# controller.net
KiCad netlist of a schematic drawn in EAGLE
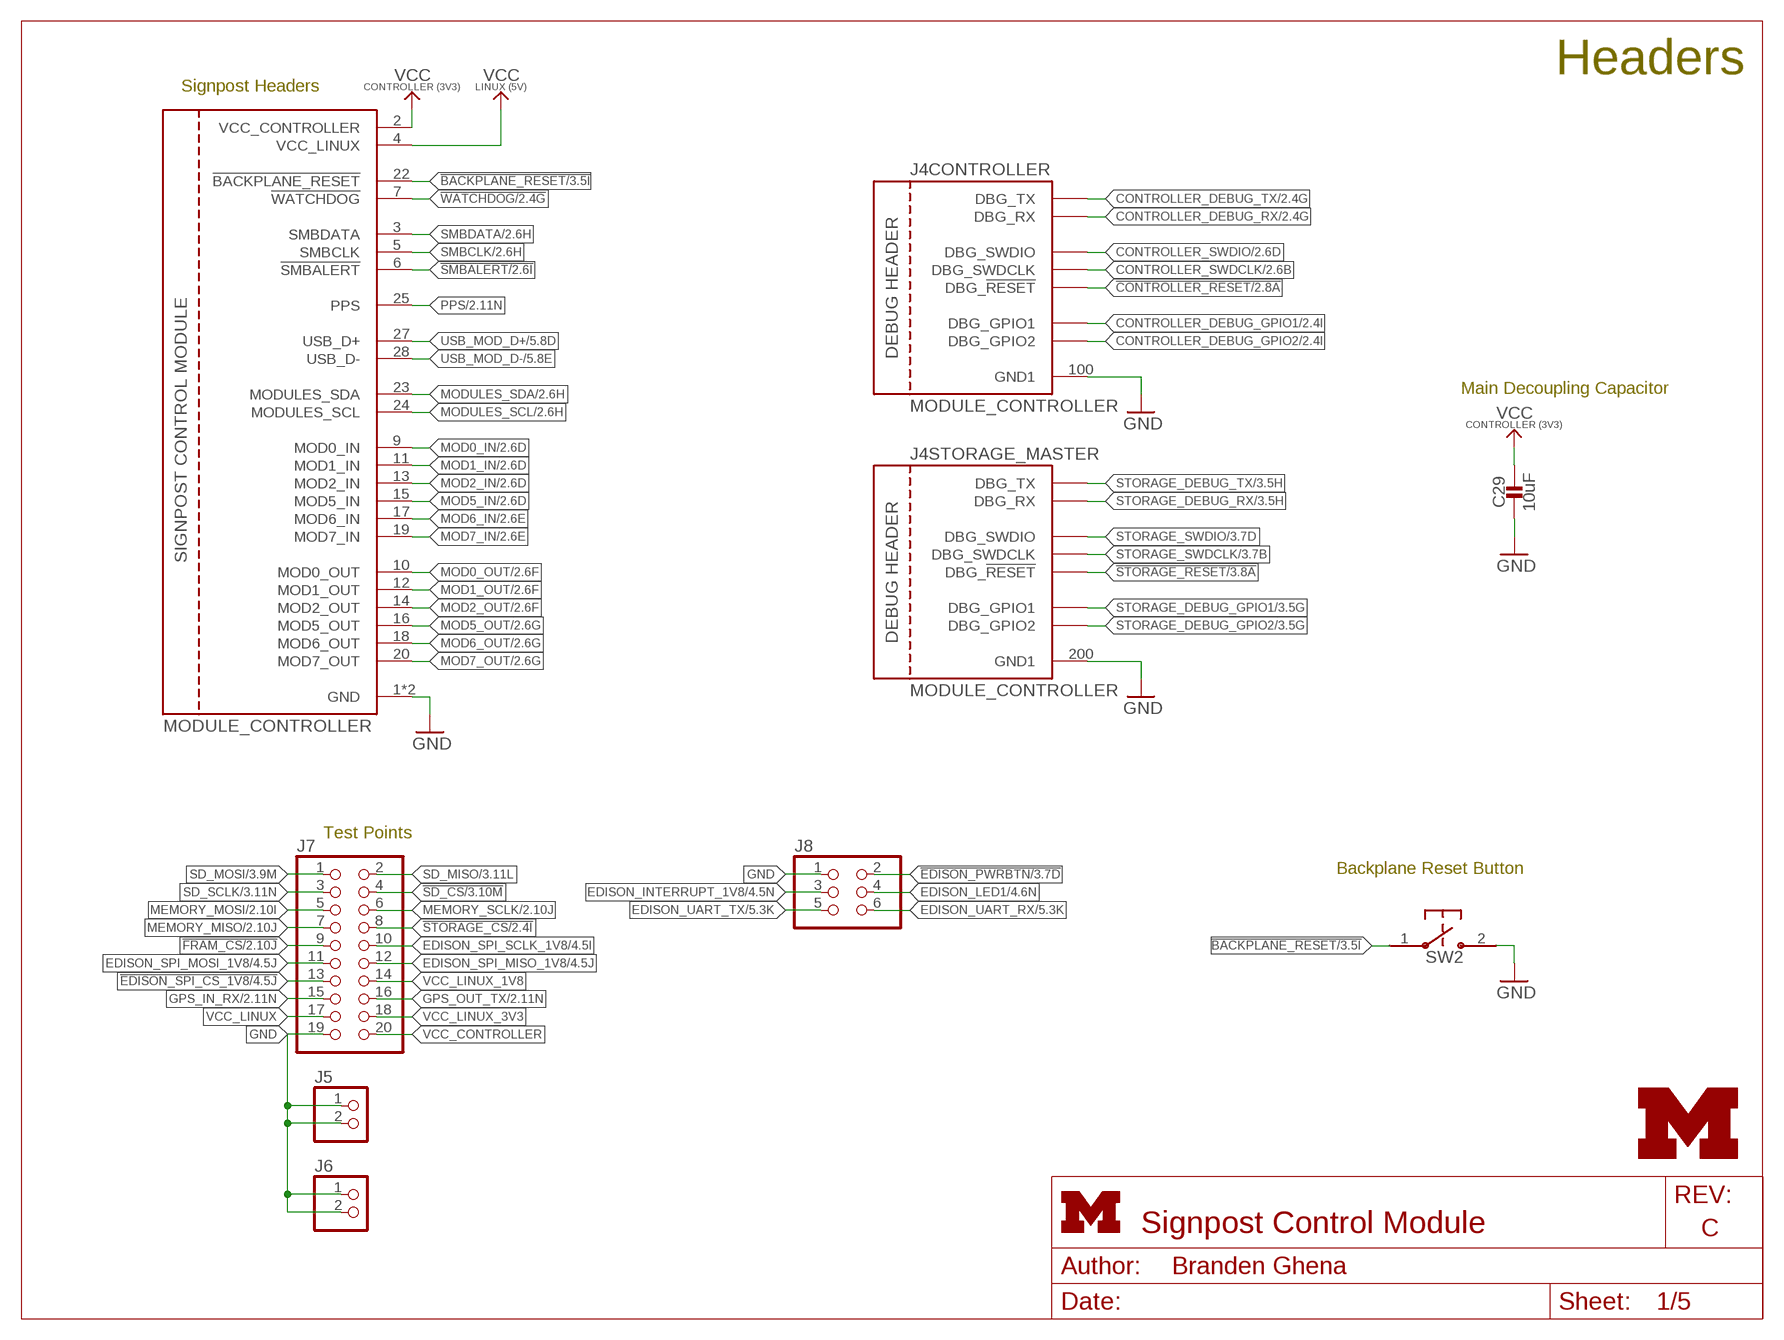
[diagram p0: schematic, sheet 1]
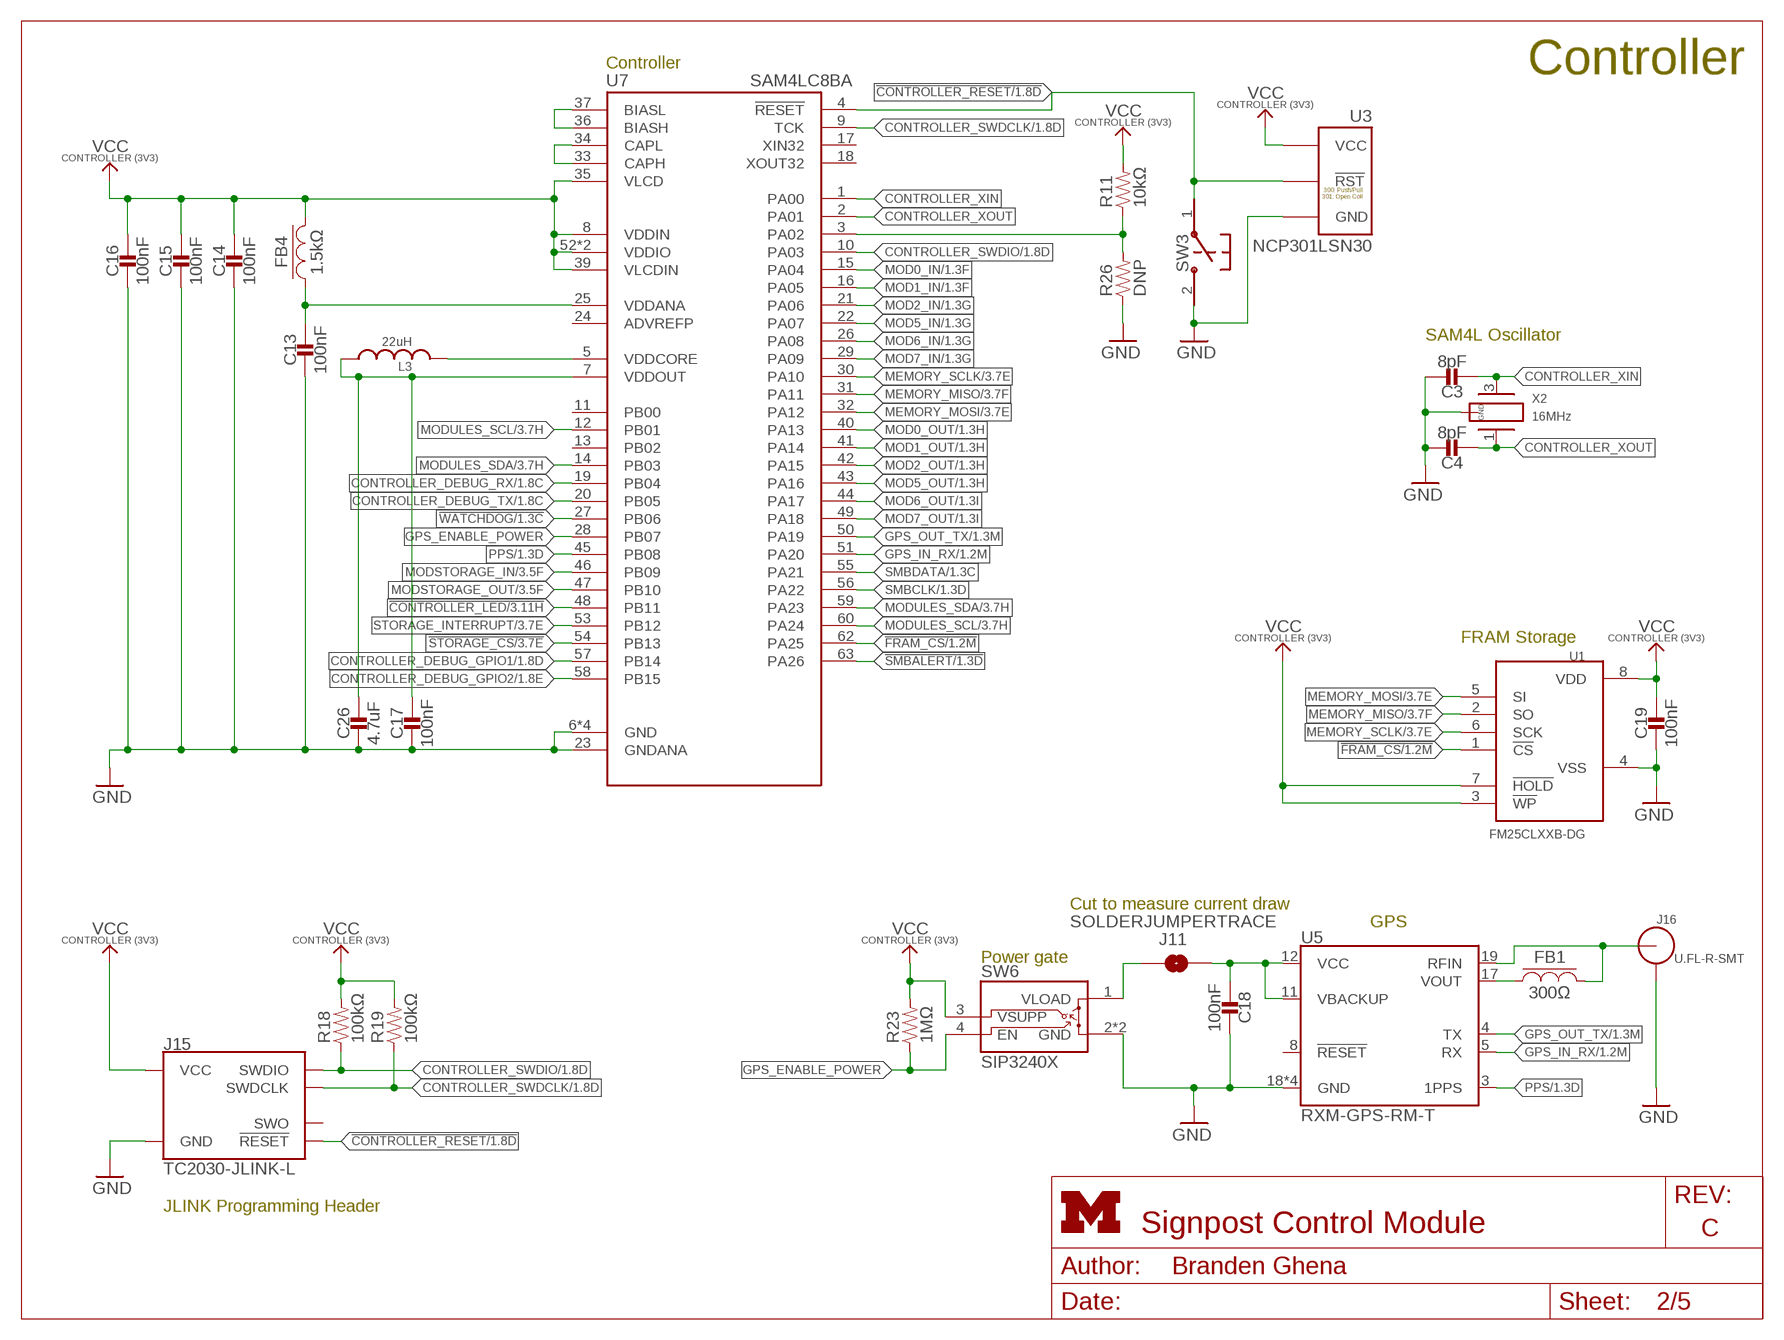
[diagram p1: schematic, sheet 2]
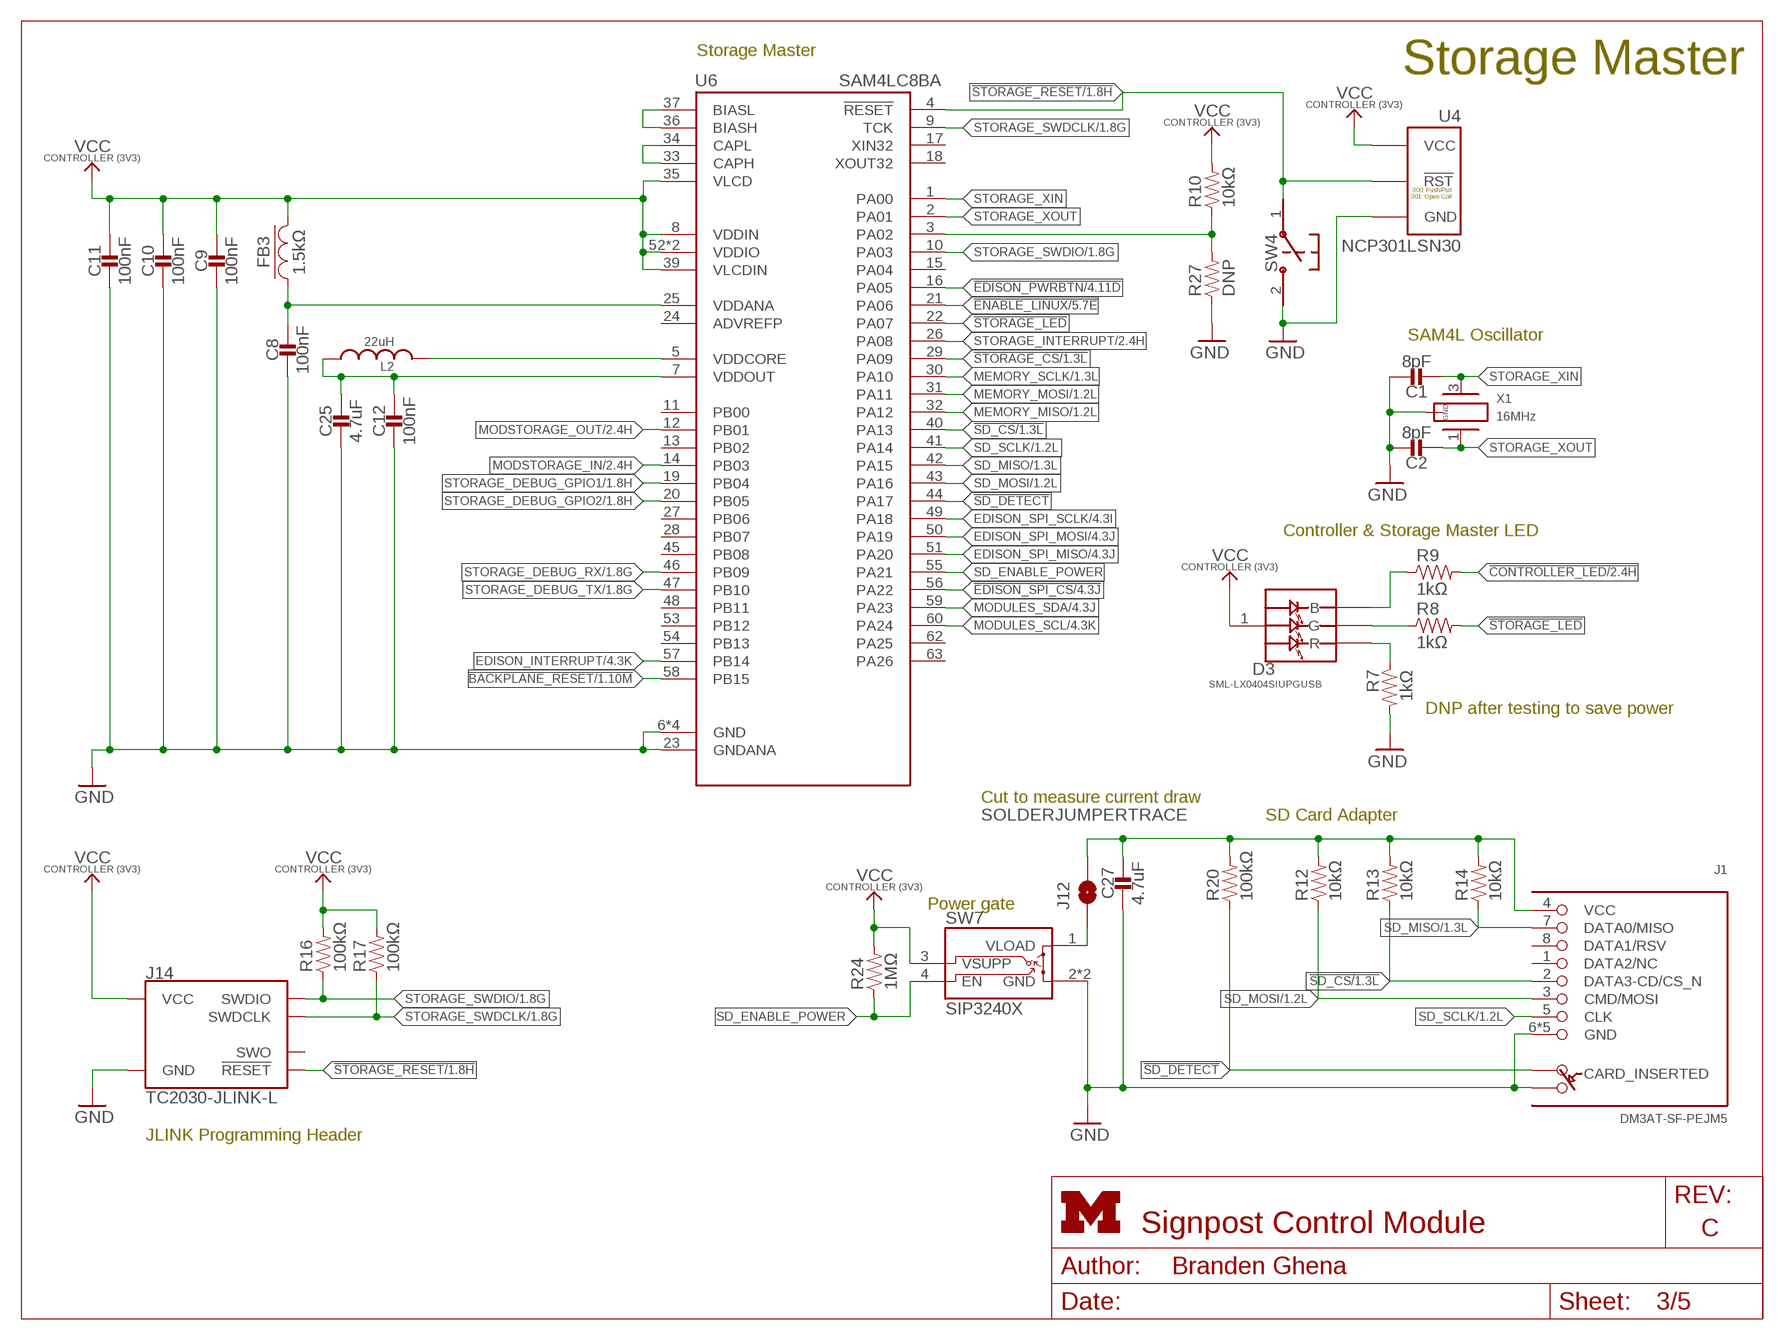
[diagram p2: schematic, sheet 3]
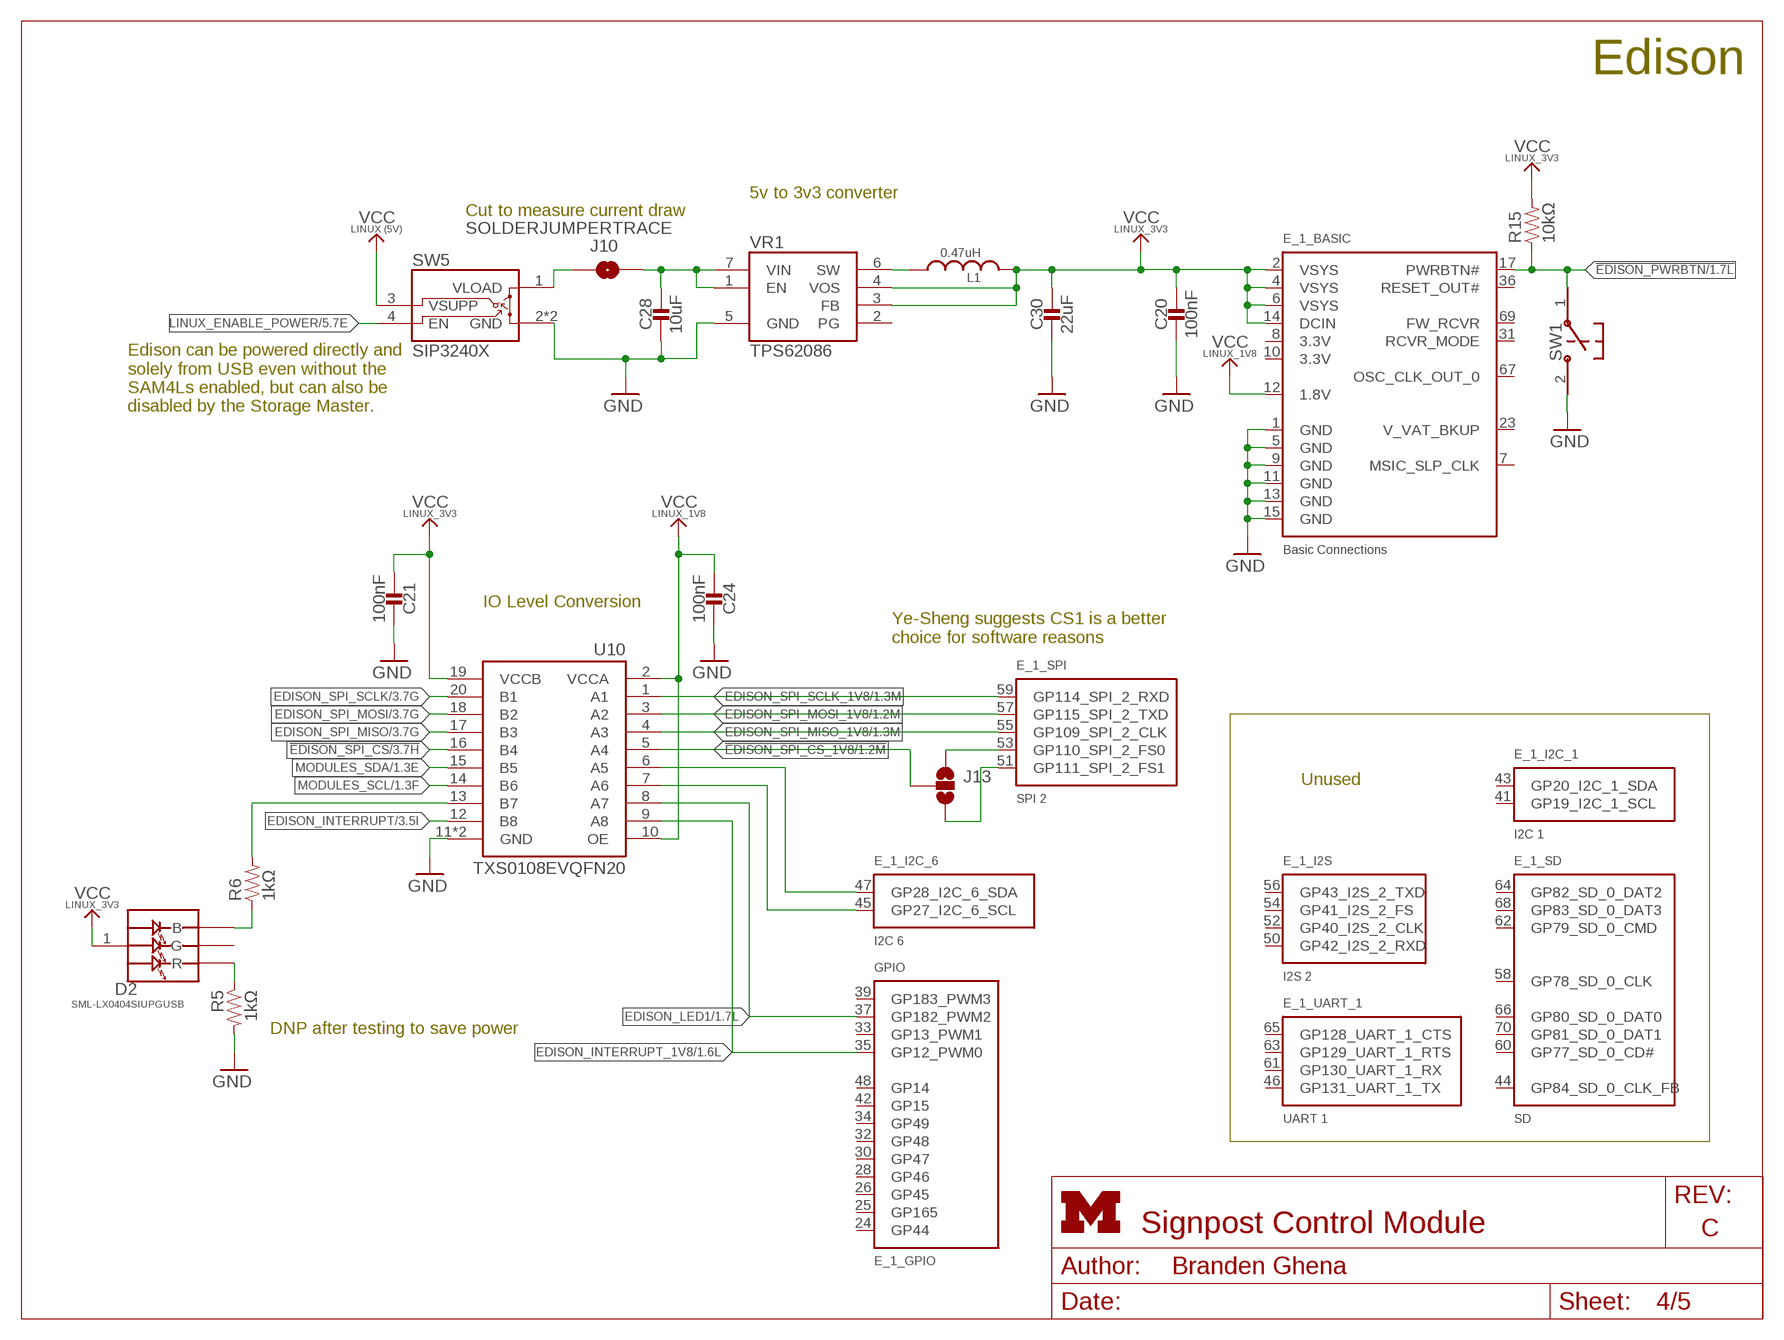
[diagram p3: schematic, sheet 4]
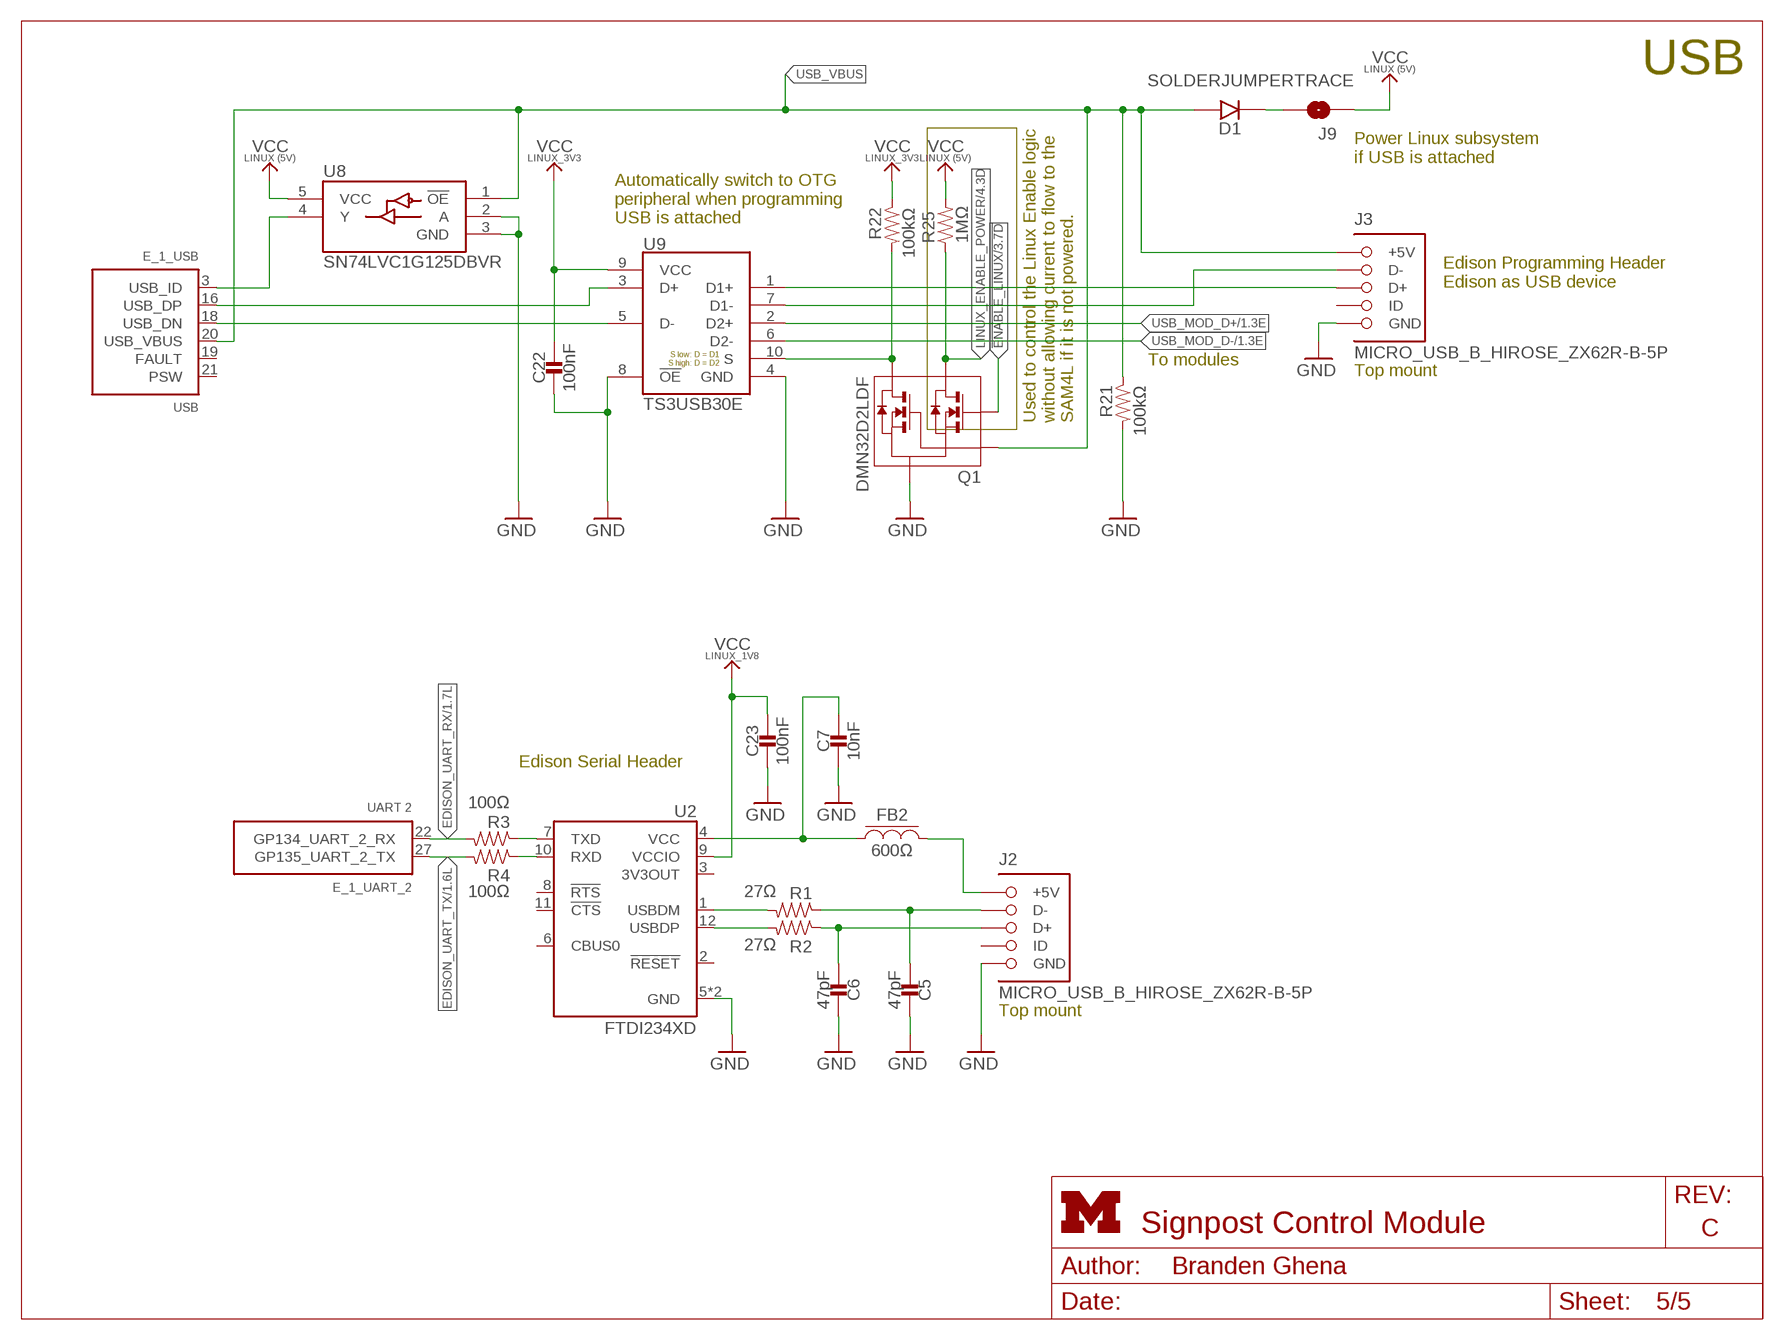
[diagram p4: schematic, sheet 5]

(export (version "E")
  (design (tool "Eeschema 10.0.6"))
  (components
    (comp (ref "C29")
      (value "10uF")
      (footprint "eagle-import:0402_CAP")
      (libsource (lib "eagle-import") (part "CAPACITOR0402_CAP"))
    )
    (comp (ref "J4")
      (value "MODULE_CONTROLLER")
      (footprint "eagle-import:MODULE_CONTROLLER")
      (libsource (lib "eagle-import") (part "MODULE_CONTROLLER"))
    )
    (comp (ref "J5")
      (value "PINHD-1X2")
      (footprint "eagle-import:1X02")
      (libsource (lib "eagle-import") (part "PINHD-1X2"))
    )
    (comp (ref "J6")
      (value "PINHD-1X2")
      (footprint "eagle-import:1X02")
      (libsource (lib "eagle-import") (part "PINHD-1X2"))
    )
    (comp (ref "J7")
      (value "PINHD-2X10")
      (footprint "eagle-import:2X10")
      (libsource (lib "eagle-import") (part "PINHD-2X10"))
    )
    (comp (ref "J8")
      (value "PINHD-2X3")
      (footprint "eagle-import:2X03")
      (libsource (lib "eagle-import") (part "PINHD-2X3"))
    )
    (comp (ref "LOGO1")
      (value "UMICH_SOLID_MEDIUM")
      (footprint "eagle-import:UMICH_SOLID_200MIL")
      (libsource (lib "eagle-import") (part "UMICH_SOLID_MEDIUM"))
    )
    (comp (ref "SW2")
      (value "B3U-1000P")
      (footprint "eagle-import:B3U-1000P")
      (libsource (lib "eagle-import") (part "B3U-1000P"))
    )
    (comp (ref "C3")
      (value "8pF")
      (footprint "eagle-import:0402_CAP")
      (libsource (lib "eagle-import") (part "CAPACITOR0402_CAP"))
    )
    (comp (ref "C4")
      (value "8pF")
      (footprint "eagle-import:0402_CAP")
      (libsource (lib "eagle-import") (part "CAPACITOR0402_CAP"))
    )
    (comp (ref "C13")
      (value "100nF")
      (footprint "eagle-import:0402_CAP")
      (libsource (lib "eagle-import") (part "CAPACITOR0402_CAP"))
    )
    (comp (ref "C14")
      (value "100nF")
      (footprint "eagle-import:0402_CAP")
      (libsource (lib "eagle-import") (part "CAPACITOR0402_CAP"))
    )
    (comp (ref "C15")
      (value "100nF")
      (footprint "eagle-import:0402_CAP")
      (libsource (lib "eagle-import") (part "CAPACITOR0402_CAP"))
    )
    (comp (ref "C16")
      (value "100nF")
      (footprint "eagle-import:0402_CAP")
      (libsource (lib "eagle-import") (part "CAPACITOR0402_CAP"))
    )
    (comp (ref "C17")
      (value "100nF")
      (footprint "eagle-import:0402_CAP")
      (libsource (lib "eagle-import") (part "CAPACITOR0402_CAP"))
    )
    (comp (ref "C18")
      (value "100nF")
      (footprint "eagle-import:0402_CAP")
      (libsource (lib "eagle-import") (part "CAPACITOR0402_CAP"))
    )
    (comp (ref "C19")
      (value "100nF")
      (footprint "eagle-import:0402_CAP")
      (libsource (lib "eagle-import") (part "CAPACITOR0402_CAP"))
    )
    (comp (ref "C26")
      (value "4.7uF")
      (footprint "eagle-import:0402_CAP")
      (libsource (lib "eagle-import") (part "CAPACITOR0402_CAP"))
    )
    (comp (ref "FB1")
      (value "300Ω")
      (footprint "eagle-import:0402_CAP")
      (libsource (lib "eagle-import") (part "FERRITE_BEAD0402"))
    )
    (comp (ref "FB4")
      (value "1.5kΩ")
      (footprint "eagle-import:0402_CAP")
      (libsource (lib "eagle-import") (part "FERRITE_BEAD0402"))
    )
    (comp (ref "J11")
      (value "SOLDERJUMPERTRACE")
      (footprint "eagle-import:SJ_2S-TRACE")
      (libsource (lib "eagle-import") (part "SOLDERJUMPERTRACE"))
    )
    (comp (ref "J15")
      (value "TC2030-JLINK-L")
      (footprint "eagle-import:TC2030-IDC")
      (libsource (lib "eagle-import") (part "TC2030-JLINK-L"))
    )
    (comp (ref "J16")
      (value "U.FL-R-SMT")
      (footprint "eagle-import:U.FL_SMT")
      (libsource (lib "eagle-import") (part "U.FL-R-SMT"))
    )
    (comp (ref "L3")
      (value "22uH")
      (footprint "eagle-import:1212")
      (libsource (lib "eagle-import") (part "LHQ3NP"))
    )
    (comp (ref "R11")
      (value "10kΩ")
      (footprint "eagle-import:0402_RES")
      (libsource (lib "eagle-import") (part "RESISTOR0402_RES"))
    )
    (comp (ref "R18")
      (value "100kΩ")
      (footprint "eagle-import:0402_RES")
      (libsource (lib "eagle-import") (part "RESISTOR0402_RES"))
    )
    (comp (ref "R19")
      (value "100kΩ")
      (footprint "eagle-import:0402_RES")
      (libsource (lib "eagle-import") (part "RESISTOR0402_RES"))
    )
    (comp (ref "R23")
      (value "1MΩ")
      (footprint "eagle-import:0402_RES")
      (libsource (lib "eagle-import") (part "RESISTOR0402_RES"))
    )
    (comp (ref "R26")
      (value "DNP")
      (footprint "eagle-import:0402_RES")
      (libsource (lib "eagle-import") (part "RESISTOR0402_RES"))
    )
    (comp (ref "SW3")
      (value "B3U-1000P")
      (footprint "eagle-import:B3U-1000P")
      (libsource (lib "eagle-import") (part "B3U-1000P"))
    )
    (comp (ref "SW6")
      (value "SIP3240X")
      (footprint "eagle-import:TDFN4")
      (libsource (lib "eagle-import") (part "SIP3240X"))
    )
    (comp (ref "U1")
      (value "FM25CLXXB-DG")
      (footprint "eagle-import:TDFN-8")
      (libsource (lib "eagle-import") (part "FM25CLXXB-DG"))
    )
    (comp (ref "U3")
      (value "NCP301LSN30")
      (footprint "eagle-import:SOT23-5")
      (libsource (lib "eagle-import") (part "NCP301LSN30"))
    )
    (comp (ref "U5")
      (value "RXM-GPS-RM-T")
      (footprint "eagle-import:RXM-GPS-RM-T")
      (libsource (lib "eagle-import") (part "RXM-GPS-RM-T"))
    )
    (comp (ref "U7")
      (value "SAM4LC8BA")
      (footprint "eagle-import:QFN-64-9MM")
      (libsource (lib "eagle-import") (part "SAM4LC8BA"))
    )
    (comp (ref "X2")
      (value "16MHz")
      (footprint "eagle-import:FHXXX")
      (libsource (lib "eagle-import") (part "FH1600015"))
    )
    (comp (ref "C20")
      (value "100nF")
      (footprint "eagle-import:0402_CAP")
      (libsource (lib "eagle-import") (part "CAPACITOR0402_CAP"))
    )
    (comp (ref "C21")
      (value "100nF")
      (footprint "eagle-import:0402_CAP")
      (libsource (lib "eagle-import") (part "CAPACITOR0402_CAP"))
    )
    (comp (ref "C24")
      (value "100nF")
      (footprint "eagle-import:0402_CAP")
      (libsource (lib "eagle-import") (part "CAPACITOR0402_CAP"))
    )
    (comp (ref "C28")
      (value "10uF")
      (footprint "eagle-import:0805_CAP")
      (libsource (lib "eagle-import") (part "CAPACITOR0805_CAP"))
    )
    (comp (ref "C30")
      (value "22uF")
      (footprint "eagle-import:0805_CAP")
      (libsource (lib "eagle-import") (part "CAPACITOR0805_CAP"))
    )
    (comp (ref "D2")
      (value "SML-LX0404SIUPGUSB")
      (footprint "eagle-import:1MM_SQ_4PAD")
      (libsource (lib "eagle-import") (part "SML-LX0404SIUPGUSB"))
    )
    (comp (ref "E_1")
      (value "EDISON_CONNECTOR_SEGMENTED")
      (footprint "eagle-import:EDISON_DAUGHTER")
      (fields (field (name "AMAZON") "B00PTVSS4A") (field (name "MOUSER") "798-DF40HC3070DS4V51"))
      (libsource (lib "eagle-import") (part "EDISON_CONNECTOR_SEGMENTED"))
    )
    (comp (ref "J10")
      (value "SOLDERJUMPERTRACE")
      (footprint "eagle-import:SJ_2S-TRACE")
      (libsource (lib "eagle-import") (part "SOLDERJUMPERTRACE"))
    )
    (comp (ref "J13")
      (value "SOLDERJUMPER_2WAYPASTE2&3")
      (footprint "eagle-import:SJ_3_PASTE2&3")
      (libsource (lib "eagle-import") (part "SOLDERJUMPER_2WAYPASTE2&3"))
    )
    (comp (ref "L1")
      (value "0.47uH")
      (footprint "eagle-import:DFE322512C")
      (libsource (lib "eagle-import") (part "INDUCTORDFE322512C"))
    )
    (comp (ref "R5")
      (value "1kΩ")
      (footprint "eagle-import:0402_RES")
      (libsource (lib "eagle-import") (part "RESISTOR0402_RES"))
    )
    (comp (ref "R6")
      (value "1kΩ")
      (footprint "eagle-import:0402_RES")
      (libsource (lib "eagle-import") (part "RESISTOR0402_RES"))
    )
    (comp (ref "R15")
      (value "10kΩ")
      (footprint "eagle-import:0402_RES")
      (libsource (lib "eagle-import") (part "RESISTOR0402_RES"))
    )
    (comp (ref "SW1")
      (value "B3U-1000P")
      (footprint "eagle-import:B3U-1000P")
      (libsource (lib "eagle-import") (part "B3U-1000P"))
    )
    (comp (ref "SW5")
      (value "SIP3240X")
      (footprint "eagle-import:TDFN4")
      (libsource (lib "eagle-import") (part "SIP3240X"))
    )
    (comp (ref "U10")
      (value "TXS0108EVQFN20")
      (footprint "eagle-import:R-PVQFN-N20")
      (libsource (lib "eagle-import") (part "TXS0108EVQFN20"))
    )
    (comp (ref "VR1")
      (value "TPS62086")
      (footprint "eagle-import:RLT0007A")
      (libsource (lib "eagle-import") (part "TPS62086"))
    )
    (comp (ref "C5")
      (value "47pF")
      (footprint "eagle-import:0402_CAP")
      (libsource (lib "eagle-import") (part "CAPACITOR0402_CAP"))
    )
    (comp (ref "C6")
      (value "47pF")
      (footprint "eagle-import:0402_CAP")
      (libsource (lib "eagle-import") (part "CAPACITOR0402_CAP"))
    )
    (comp (ref "C7")
      (value "10nF")
      (footprint "eagle-import:0402_CAP")
      (libsource (lib "eagle-import") (part "CAPACITOR0402_CAP"))
    )
    (comp (ref "C22")
      (value "100nF")
      (footprint "eagle-import:0402_CAP")
      (libsource (lib "eagle-import") (part "CAPACITOR0402_CAP"))
    )
    (comp (ref "C23")
      (value "100nF")
      (footprint "eagle-import:0402_CAP")
      (libsource (lib "eagle-import") (part "CAPACITOR0402_CAP"))
    )
    (comp (ref "D1")
      (value "DIODE")
      (footprint "eagle-import:0805_DIODE")
      (libsource (lib "eagle-import") (part "DIODE"))
    )
    (comp (ref "FB2")
      (value "600Ω")
      (footprint "eagle-import:0805_CAP")
      (libsource (lib "eagle-import") (part "FERRITE_BEAD0805"))
    )
    (comp (ref "J2")
      (value "MICRO_USB_B_HIROSE_ZX62R-B-5P")
      (footprint "eagle-import:USB_MICRO_B-HIROSE-ZX62R-B-5P")
      (fields (field (name "DIGIKEY") "H125274CT-ND"))
      (libsource (lib "eagle-import") (part "MICRO_USB_B_HIROSE_ZX62R-B-5P"))
    )
    (comp (ref "J3")
      (value "MICRO_USB_B_HIROSE_ZX62R-B-5P")
      (footprint "eagle-import:USB_MICRO_B-HIROSE-ZX62R-B-5P")
      (fields (field (name "DIGIKEY") "H125274CT-ND"))
      (libsource (lib "eagle-import") (part "MICRO_USB_B_HIROSE_ZX62R-B-5P"))
    )
    (comp (ref "J9")
      (value "SOLDERJUMPERTRACE")
      (footprint "eagle-import:SJ_2S-TRACE")
      (libsource (lib "eagle-import") (part "SOLDERJUMPERTRACE"))
    )
    (comp (ref "Q1")
      (value "DMN32D2LDF")
      (footprint "eagle-import:SOT353")
      (libsource (lib "eagle-import") (part "DMN32D2LDF"))
    )
    (comp (ref "R1")
      (value "27Ω")
      (footprint "eagle-import:0402_RES")
      (libsource (lib "eagle-import") (part "RESISTOR0402_RES"))
    )
    (comp (ref "R2")
      (value "27Ω")
      (footprint "eagle-import:0402_RES")
      (libsource (lib "eagle-import") (part "RESISTOR0402_RES"))
    )
    (comp (ref "R3")
      (value "100Ω")
      (footprint "eagle-import:0402_RES")
      (libsource (lib "eagle-import") (part "RESISTOR0402_RES"))
    )
    (comp (ref "R4")
      (value "100Ω")
      (footprint "eagle-import:0402_RES")
      (libsource (lib "eagle-import") (part "RESISTOR0402_RES"))
    )
    (comp (ref "R21")
      (value "100kΩ")
      (footprint "eagle-import:0402_RES")
      (libsource (lib "eagle-import") (part "RESISTOR0402_RES"))
    )
    (comp (ref "R22")
      (value "100kΩ")
      (footprint "eagle-import:0402_RES")
      (libsource (lib "eagle-import") (part "RESISTOR0402_RES"))
    )
    (comp (ref "R25")
      (value "1MΩ")
      (footprint "eagle-import:0402_RES")
      (libsource (lib "eagle-import") (part "RESISTOR0402_RES"))
    )
    (comp (ref "U2")
      (value "FTDI234XD")
      (footprint "eagle-import:DFN-12_3MM")
      (libsource (lib "eagle-import") (part "FTDI234XD"))
    )
    (comp (ref "U8")
      (value "SN74LVC1G125DBVR")
      (footprint "eagle-import:SOT-23-5")
      (libsource (lib "eagle-import") (part "SN74LVC1G125DBVR"))
    )
    (comp (ref "U9")
      (value "TS3USB30E")
      (footprint "eagle-import:UQFN-10")
      (libsource (lib "eagle-import") (part "TS3USB30E"))
    )
    (comp (ref "C1")
      (value "8pF")
      (footprint "eagle-import:0402_CAP")
      (libsource (lib "eagle-import") (part "CAPACITOR0402_CAP"))
    )
    (comp (ref "C2")
      (value "8pF")
      (footprint "eagle-import:0402_CAP")
      (libsource (lib "eagle-import") (part "CAPACITOR0402_CAP"))
    )
    (comp (ref "C8")
      (value "100nF")
      (footprint "eagle-import:0402_CAP")
      (libsource (lib "eagle-import") (part "CAPACITOR0402_CAP"))
    )
    (comp (ref "C9")
      (value "100nF")
      (footprint "eagle-import:0402_CAP")
      (libsource (lib "eagle-import") (part "CAPACITOR0402_CAP"))
    )
    (comp (ref "C10")
      (value "100nF")
      (footprint "eagle-import:0402_CAP")
      (libsource (lib "eagle-import") (part "CAPACITOR0402_CAP"))
    )
    (comp (ref "C11")
      (value "100nF")
      (footprint "eagle-import:0402_CAP")
      (libsource (lib "eagle-import") (part "CAPACITOR0402_CAP"))
    )
    (comp (ref "C12")
      (value "100nF")
      (footprint "eagle-import:0402_CAP")
      (libsource (lib "eagle-import") (part "CAPACITOR0402_CAP"))
    )
    (comp (ref "C25")
      (value "4.7uF")
      (footprint "eagle-import:0402_CAP")
      (libsource (lib "eagle-import") (part "CAPACITOR0402_CAP"))
    )
    (comp (ref "C27")
      (value "4.7uF")
      (footprint "eagle-import:0402_CAP")
      (libsource (lib "eagle-import") (part "CAPACITOR0402_CAP"))
    )
    (comp (ref "D3")
      (value "SML-LX0404SIUPGUSB")
      (footprint "eagle-import:1MM_SQ_4PAD")
      (libsource (lib "eagle-import") (part "SML-LX0404SIUPGUSB"))
    )
    (comp (ref "FB3")
      (value "1.5kΩ")
      (footprint "eagle-import:0402_CAP")
      (libsource (lib "eagle-import") (part "FERRITE_BEAD0402"))
    )
    (comp (ref "J1")
      (value "DM3AT-SF-PEJM5")
      (footprint "eagle-import:DM3AT-SF-PEJM5")
      (libsource (lib "eagle-import") (part "DM3AT-SF-PEJM5"))
    )
    (comp (ref "J12")
      (value "SOLDERJUMPERTRACE")
      (footprint "eagle-import:SJ_2S-TRACE")
      (libsource (lib "eagle-import") (part "SOLDERJUMPERTRACE"))
    )
    (comp (ref "J14")
      (value "TC2030-JLINK-L")
      (footprint "eagle-import:TC2030-IDC")
      (libsource (lib "eagle-import") (part "TC2030-JLINK-L"))
    )
    (comp (ref "L2")
      (value "22uH")
      (footprint "eagle-import:1212")
      (libsource (lib "eagle-import") (part "LHQ3NP"))
    )
    (comp (ref "R7")
      (value "1kΩ")
      (footprint "eagle-import:0402_RES")
      (libsource (lib "eagle-import") (part "RESISTOR0402_RES"))
    )
    (comp (ref "R8")
      (value "1kΩ")
      (footprint "eagle-import:0402_RES")
      (libsource (lib "eagle-import") (part "RESISTOR0402_RES"))
    )
    (comp (ref "R9")
      (value "1kΩ")
      (footprint "eagle-import:0402_RES")
      (libsource (lib "eagle-import") (part "RESISTOR0402_RES"))
    )
    (comp (ref "R10")
      (value "10kΩ")
      (footprint "eagle-import:0402_RES")
      (libsource (lib "eagle-import") (part "RESISTOR0402_RES"))
    )
    (comp (ref "R12")
      (value "10kΩ")
      (footprint "eagle-import:0402_RES")
      (libsource (lib "eagle-import") (part "RESISTOR0402_RES"))
    )
    (comp (ref "R13")
      (value "10kΩ")
      (footprint "eagle-import:0402_RES")
      (libsource (lib "eagle-import") (part "RESISTOR0402_RES"))
    )
    (comp (ref "R14")
      (value "10kΩ")
      (footprint "eagle-import:0402_RES")
      (libsource (lib "eagle-import") (part "RESISTOR0402_RES"))
    )
    (comp (ref "R16")
      (value "100kΩ")
      (footprint "eagle-import:0402_RES")
      (libsource (lib "eagle-import") (part "RESISTOR0402_RES"))
    )
    (comp (ref "R17")
      (value "100kΩ")
      (footprint "eagle-import:0402_RES")
      (libsource (lib "eagle-import") (part "RESISTOR0402_RES"))
    )
    (comp (ref "R20")
      (value "100kΩ")
      (footprint "eagle-import:0402_RES")
      (libsource (lib "eagle-import") (part "RESISTOR0402_RES"))
    )
    (comp (ref "R24")
      (value "1MΩ")
      (footprint "eagle-import:0402_RES")
      (libsource (lib "eagle-import") (part "RESISTOR0402_RES"))
    )
    (comp (ref "R27")
      (value "DNP")
      (footprint "eagle-import:0402_RES")
      (libsource (lib "eagle-import") (part "RESISTOR0402_RES"))
    )
    (comp (ref "SW4")
      (value "B3U-1000P")
      (footprint "eagle-import:B3U-1000P")
      (libsource (lib "eagle-import") (part "B3U-1000P"))
    )
    (comp (ref "SW7")
      (value "SIP3240X")
      (footprint "eagle-import:TDFN4")
      (libsource (lib "eagle-import") (part "SIP3240X"))
    )
    (comp (ref "U4")
      (value "NCP301LSN30")
      (footprint "eagle-import:SOT23-5")
      (libsource (lib "eagle-import") (part "NCP301LSN30"))
    )
    (comp (ref "U6")
      (value "SAM4LC8BA")
      (footprint "eagle-import:QFN-64-9MM")
      (libsource (lib "eagle-import") (part "SAM4LC8BA"))
    )
    (comp (ref "X1")
      (value "16MHz")
      (footprint "eagle-import:FHXXX")
      (libsource (lib "eagle-import") (part "FH1600015"))
    )
  )
  (nets
    (net (code "1") (name "CONTROLLER_DEBUG_GPIO1") (class "Default")
      (node (ref "J4") (pin "101") (pinfunction "DBG_GPIO1_101") (pintype "bidirectional"))
      (node (ref "U7") (pin "57") (pinfunction "PB14_57") (pintype "bidirectional"))
    )
    (net (code "2") (name "CONTROLLER_DEBUG_GPIO2") (class "Default")
      (node (ref "J4") (pin "104") (pinfunction "DBG_GPIO2_104") (pintype "bidirectional"))
      (node (ref "U7") (pin "58") (pinfunction "PB15_58") (pintype "bidirectional"))
    )
    (net (code "3") (name "CONTROLLER_DEBUG_RX") (class "Default")
      (node (ref "J4") (pin "103") (pinfunction "DBG_RX_103") (pintype "bidirectional"))
      (node (ref "U7") (pin "19") (pinfunction "PB04_19") (pintype "bidirectional"))
    )
    (net (code "4") (name "CONTROLLER_DEBUG_TX") (class "Default")
      (node (ref "J4") (pin "102") (pinfunction "DBG_TX_102") (pintype "bidirectional"))
      (node (ref "U7") (pin "20") (pinfunction "PB05_20") (pintype "bidirectional"))
    )
    (net (code "5") (name "CONTROLLER_SWDCLK") (class "Default")
      (node (ref "J15") (pin "4") (pinfunction "SWDCLK_4") (pintype "bidirectional"))
      (node (ref "J4") (pin "106") (pinfunction "DBG_SWDCLK_106") (pintype "bidirectional"))
      (node (ref "R19") (pin "1") (pinfunction "1_1") (pintype "passive"))
      (node (ref "U7") (pin "9") (pinfunction "TCK_9") (pintype "bidirectional"))
    )
    (net (code "6") (name "CONTROLLER_SWDIO") (class "Default")
      (node (ref "J15") (pin "2") (pinfunction "SWDIO_2") (pintype "bidirectional"))
      (node (ref "J4") (pin "107") (pinfunction "DBG_SWDIO_107") (pintype "bidirectional"))
      (node (ref "R18") (pin "1") (pinfunction "1_1") (pintype "passive"))
      (node (ref "U7") (pin "10") (pinfunction "PA03_10") (pintype "bidirectional"))
    )
    (net (code "7") (name "CONTROLLER_XIN") (class "Default")
      (node (ref "C3") (pin "1") (pinfunction "1_1") (pintype "bidirectional"))
      (node (ref "U7") (pin "1") (pinfunction "PA00_1") (pintype "bidirectional"))
      (node (ref "X2") (pin "3") (pinfunction "2_3") (pintype "bidirectional"))
    )
    (net (code "8") (name "CONTROLLER_XOUT") (class "Default")
      (node (ref "C4") (pin "1") (pinfunction "1_1") (pintype "bidirectional"))
      (node (ref "U7") (pin "2") (pinfunction "PA01_2") (pintype "bidirectional"))
      (node (ref "X2") (pin "1") (pinfunction "1_1") (pintype "bidirectional"))
    )
    (net (code "9") (name "EDISON_INTERRUPT") (class "Default")
      (node (ref "U10") (pin "12") (pinfunction "B8_12") (pintype "bidirectional"))
      (node (ref "U6") (pin "57") (pinfunction "PB14_57") (pintype "bidirectional"))
    )
    (net (code "10") (name "EDISON_INTERRUPT_1V8") (class "Default")
      (node (ref "E_1") (pin "35") (pinfunction "GP12_PWM0_35") (pintype "bidirectional"))
      (node (ref "J8") (pin "3") (pinfunction "3_3") (pintype "passive"))
      (node (ref "U10") (pin "9") (pinfunction "A8_9") (pintype "bidirectional"))
    )
    (net (code "11") (name "EDISON_LED1") (class "Default")
      (node (ref "E_1") (pin "37") (pinfunction "GP182_PWM2_37") (pintype "bidirectional"))
      (node (ref "J8") (pin "4") (pinfunction "4_4") (pintype "passive"))
      (node (ref "U10") (pin "8") (pinfunction "A7_8") (pintype "bidirectional"))
    )
    (net (code "12") (name "EDISON_SPI_MISO") (class "Default")
      (node (ref "U10") (pin "17") (pinfunction "B3_17") (pintype "bidirectional"))
      (node (ref "U6") (pin "51") (pinfunction "PA20_51") (pintype "bidirectional"))
    )
    (net (code "13") (name "EDISON_SPI_MISO_1V8") (class "Default")
      (node (ref "E_1") (pin "55") (pinfunction "GP109_SPI_2_CLK_55") (pintype "bidirectional"))
      (node (ref "J7") (pin "12") (pinfunction "12_12") (pintype "passive"))
      (node (ref "U10") (pin "4") (pinfunction "A3_4") (pintype "bidirectional"))
    )
    (net (code "14") (name "EDISON_SPI_MOSI") (class "Default")
      (node (ref "U10") (pin "18") (pinfunction "B2_18") (pintype "bidirectional"))
      (node (ref "U6") (pin "50") (pinfunction "PA19_50") (pintype "bidirectional"))
    )
    (net (code "15") (name "EDISON_SPI_MOSI_1V8") (class "Default")
      (node (ref "E_1") (pin "57") (pinfunction "GP115_SPI_2_TXD_57") (pintype "bidirectional"))
      (node (ref "J7") (pin "11") (pinfunction "11_11") (pintype "passive"))
      (node (ref "U10") (pin "3") (pinfunction "A2_3") (pintype "bidirectional"))
    )
    (net (code "16") (name "EDISON_SPI_SCLK") (class "Default")
      (node (ref "U10") (pin "20") (pinfunction "B1_20") (pintype "bidirectional"))
      (node (ref "U6") (pin "49") (pinfunction "PA18_49") (pintype "bidirectional"))
    )
    (net (code "17") (name "EDISON_SPI_SCLK_1V8") (class "Default")
      (node (ref "E_1") (pin "59") (pinfunction "GP114_SPI_2_RXD_59") (pintype "bidirectional"))
      (node (ref "J7") (pin "10") (pinfunction "10_10") (pintype "passive"))
      (node (ref "U10") (pin "1") (pinfunction "A1_1") (pintype "bidirectional"))
    )
    (net (code "18") (name "EDISON_UART_RX") (class "Default")
      (node (ref "E_1") (pin "22") (pinfunction "GP134_UART_2_RX_22") (pintype "bidirectional"))
      (node (ref "J8") (pin "6") (pinfunction "6_6") (pintype "passive"))
      (node (ref "R3") (pin "2") (pinfunction "2_2") (pintype "passive"))
    )
    (net (code "19") (name "EDISON_UART_TX") (class "Default")
      (node (ref "E_1") (pin "27") (pinfunction "GP135_UART_2_TX_27") (pintype "bidirectional"))
      (node (ref "J8") (pin "5") (pinfunction "5_5") (pintype "passive"))
      (node (ref "R4") (pin "2") (pinfunction "2_2") (pintype "passive"))
    )
    (net (code "20") (name "GND") (class "Default")
      (node (ref "C1") (pin "2") (pinfunction "2_2") (pintype "bidirectional"))
      (node (ref "C10") (pin "2") (pinfunction "2_2") (pintype "bidirectional"))
      (node (ref "C11") (pin "2") (pinfunction "2_2") (pintype "bidirectional"))
      (node (ref "C12") (pin "2") (pinfunction "2_2") (pintype "bidirectional"))
      (node (ref "C13") (pin "2") (pinfunction "2_2") (pintype "bidirectional"))
      (node (ref "C14") (pin "2") (pinfunction "2_2") (pintype "bidirectional"))
      (node (ref "C15") (pin "2") (pinfunction "2_2") (pintype "bidirectional"))
      (node (ref "C16") (pin "2") (pinfunction "2_2") (pintype "bidirectional"))
      (node (ref "C17") (pin "2") (pinfunction "2_2") (pintype "bidirectional"))
      (node (ref "C18") (pin "2") (pinfunction "2_2") (pintype "bidirectional"))
      (node (ref "C19") (pin "2") (pinfunction "2_2") (pintype "bidirectional"))
      (node (ref "C2") (pin "2") (pinfunction "2_2") (pintype "bidirectional"))
      (node (ref "C20") (pin "2") (pinfunction "2_2") (pintype "bidirectional"))
      (node (ref "C21") (pin "1") (pinfunction "1_1") (pintype "bidirectional"))
      (node (ref "C22") (pin "2") (pinfunction "2_2") (pintype "bidirectional"))
      (node (ref "C23") (pin "2") (pinfunction "2_2") (pintype "bidirectional"))
      (node (ref "C24") (pin "1") (pinfunction "1_1") (pintype "bidirectional"))
      (node (ref "C25") (pin "2") (pinfunction "2_2") (pintype "bidirectional"))
      (node (ref "C26") (pin "2") (pinfunction "2_2") (pintype "bidirectional"))
      (node (ref "C27") (pin "2") (pinfunction "2_2") (pintype "bidirectional"))
      (node (ref "C28") (pin "P$2") (pinfunction "2_P$2") (pintype "bidirectional"))
      (node (ref "C29") (pin "2") (pinfunction "2_2") (pintype "bidirectional"))
      (node (ref "C3") (pin "2") (pinfunction "2_2") (pintype "bidirectional"))
      (node (ref "C30") (pin "P$2") (pinfunction "2_P$2") (pintype "bidirectional"))
      (node (ref "C4") (pin "2") (pinfunction "2_2") (pintype "bidirectional"))
      (node (ref "C5") (pin "2") (pinfunction "2_2") (pintype "bidirectional"))
      (node (ref "C6") (pin "2") (pinfunction "2_2") (pintype "bidirectional"))
      (node (ref "C7") (pin "2") (pinfunction "2_2") (pintype "bidirectional"))
      (node (ref "C8") (pin "2") (pinfunction "2_2") (pintype "bidirectional"))
      (node (ref "C9") (pin "2") (pinfunction "2_2") (pintype "bidirectional"))
      (node (ref "E_1") (pin "1") (pinfunction "GND_1") (pintype "bidirectional"))
      (node (ref "E_1") (pin "11") (pinfunction "GND_11") (pintype "bidirectional"))
      (node (ref "E_1") (pin "13") (pinfunction "GND_13") (pintype "bidirectional"))
      (node (ref "E_1") (pin "15") (pinfunction "GND_15") (pintype "bidirectional"))
      (node (ref "E_1") (pin "5") (pinfunction "GND_5") (pintype "bidirectional"))
      (node (ref "E_1") (pin "9") (pinfunction "GND_9") (pintype "bidirectional"))
      (node (ref "J1") (pin "6") (pinfunction "GND_6") (pintype "bidirectional"))
      (node (ref "J1") (pin "B") (pinfunction "B_B") (pintype "bidirectional"))
      (node (ref "J1") (pin "MOUNT0") (pinfunction "GND_MOUNT0") (pintype "bidirectional"))
      (node (ref "J1") (pin "MOUNT1") (pinfunction "GND_MOUNT1") (pintype "bidirectional"))
      (node (ref "J1") (pin "MOUNT2") (pinfunction "GND_MOUNT2") (pintype "bidirectional"))
      (node (ref "J1") (pin "MOUNT3") (pinfunction "GND_MOUNT3") (pintype "bidirectional"))
      (node (ref "J14") (pin "5") (pinfunction "GND_5") (pintype "bidirectional"))
      (node (ref "J15") (pin "5") (pinfunction "GND_5") (pintype "bidirectional"))
      (node (ref "J16") (pin "GND1") (pinfunction "P$2_GND1") (pintype "bidirectional"))
      (node (ref "J16") (pin "GND2") (pinfunction "P$2_GND2") (pintype "bidirectional"))
      (node (ref "J2") (pin "5") (pinfunction "GND_5") (pintype "bidirectional"))
      (node (ref "J3") (pin "5") (pinfunction "GND_5") (pintype "bidirectional"))
      (node (ref "J4") (pin "1") (pinfunction "GND_1") (pintype "bidirectional"))
      (node (ref "J4") (pin "100") (pinfunction "GND1_100") (pintype "bidirectional"))
      (node (ref "J4") (pin "200") (pinfunction "GND1_200") (pintype "bidirectional"))
      (node (ref "J4") (pin "21") (pinfunction "GND_21") (pintype "bidirectional"))
      (node (ref "J5") (pin "1") (pinfunction "1_1") (pintype "passive"))
      (node (ref "J5") (pin "2") (pinfunction "2_2") (pintype "passive"))
      (node (ref "J6") (pin "1") (pinfunction "1_1") (pintype "passive"))
      (node (ref "J6") (pin "2") (pinfunction "2_2") (pintype "passive"))
      (node (ref "J7") (pin "19") (pinfunction "19_19") (pintype "passive"))
      (node (ref "J8") (pin "1") (pinfunction "1_1") (pintype "passive"))
      (node (ref "Q1") (pin "S") (pinfunction "S_S") (pintype "bidirectional"))
      (node (ref "R21") (pin "2") (pinfunction "2_2") (pintype "passive"))
      (node (ref "R26") (pin "1") (pinfunction "1_1") (pintype "passive"))
      (node (ref "R27") (pin "1") (pinfunction "1_1") (pintype "passive"))
      (node (ref "R5") (pin "2") (pinfunction "2_2") (pintype "passive"))
      (node (ref "R7") (pin "2") (pinfunction "2_2") (pintype "passive"))
      (node (ref "SW1") (pin "2") (pinfunction "P$2_2") (pintype "passive"))
      (node (ref "SW2") (pin "2") (pinfunction "P$2_2") (pintype "passive"))
      (node (ref "SW3") (pin "2") (pinfunction "P$2_2") (pintype "passive"))
      (node (ref "SW4") (pin "2") (pinfunction "P$2_2") (pintype "passive"))
      (node (ref "SW5") (pin "2") (pinfunction "GND_2") (pintype "bidirectional"))
      (node (ref "SW5") (pin "PAD") (pinfunction "GND_PAD") (pintype "bidirectional"))
      (node (ref "SW6") (pin "2") (pinfunction "GND_2") (pintype "bidirectional"))
      (node (ref "SW6") (pin "PAD") (pinfunction "GND_PAD") (pintype "bidirectional"))
      (node (ref "SW7") (pin "2") (pinfunction "GND_2") (pintype "bidirectional"))
      (node (ref "SW7") (pin "PAD") (pinfunction "GND_PAD") (pintype "bidirectional"))
      (node (ref "U1") (pin "4") (pinfunction "VSS_4") (pintype "bidirectional"))
      (node (ref "U10") (pin "11") (pinfunction "GND_11") (pintype "bidirectional"))
      (node (ref "U10") (pin "THERMAL") (pinfunction "GND_THERMAL") (pintype "bidirectional"))
      (node (ref "U2") (pin "13") (pinfunction "GND_13") (pintype "bidirectional"))
      (node (ref "U2") (pin "5") (pinfunction "GND_5") (pintype "bidirectional"))
      (node (ref "U3") (pin "3") (pinfunction "GND_3") (pintype "bidirectional"))
      (node (ref "U4") (pin "3") (pinfunction "GND_3") (pintype "bidirectional"))
      (node (ref "U5") (pin "18") (pinfunction "GND_18") (pintype "bidirectional"))
      (node (ref "U5") (pin "20") (pinfunction "GND_20") (pintype "bidirectional"))
      (node (ref "U5") (pin "21") (pinfunction "GND_21") (pintype "bidirectional"))
      (node (ref "U5") (pin "22") (pinfunction "GND_22") (pintype "bidirectional"))
      (node (ref "U6") (pin "23") (pinfunction "GNDANA_23") (pintype "power_in"))
      (node (ref "U6") (pin "38") (pinfunction "GND_38") (pintype "power_in"))
      (node (ref "U6") (pin "6") (pinfunction "GND_6") (pintype "power_in"))
      (node (ref "U6") (pin "64") (pinfunction "GND_64") (pintype "power_in"))
      (node (ref "U6") (pin "GND") (pinfunction "GND_GND") (pintype "power_in"))
      (node (ref "U7") (pin "23") (pinfunction "GNDANA_23") (pintype "power_in"))
      (node (ref "U7") (pin "38") (pinfunction "GND_38") (pintype "power_in"))
      (node (ref "U7") (pin "6") (pinfunction "GND_6") (pintype "power_in"))
      (node (ref "U7") (pin "64") (pinfunction "GND_64") (pintype "power_in"))
      (node (ref "U7") (pin "GND") (pinfunction "GND_GND") (pintype "power_in"))
      (node (ref "U8") (pin "2") (pinfunction "A_2") (pintype "bidirectional"))
      (node (ref "U8") (pin "3") (pinfunction "GND_3") (pintype "power_in"))
      (node (ref "U9") (pin "4") (pinfunction "GND_4") (pintype "bidirectional"))
      (node (ref "U9") (pin "8") (pinfunction "~{OE}_8") (pintype "bidirectional"))
      (node (ref "VR1") (pin "5") (pinfunction "GND_5") (pintype "bidirectional"))
      (node (ref "X1") (pin "2") (pinfunction "GND_2") (pintype "bidirectional"))
      (node (ref "X1") (pin "4") (pinfunction "GND_4") (pintype "bidirectional"))
      (node (ref "X2") (pin "2") (pinfunction "GND_2") (pintype "bidirectional"))
      (node (ref "X2") (pin "4") (pinfunction "GND_4") (pintype "bidirectional"))
    )
    (net (code "21") (name "GPS_ENABLE_POWER") (class "Default")
      (node (ref "R23") (pin "1") (pinfunction "1_1") (pintype "passive"))
      (node (ref "SW6") (pin "4") (pinfunction "EN_4") (pintype "bidirectional"))
      (node (ref "U7") (pin "28") (pinfunction "PB07_28") (pintype "bidirectional"))
    )
    (net (code "22") (name "GPS_IN_RX") (class "Default")
      (node (ref "J7") (pin "15") (pinfunction "15_15") (pintype "passive"))
      (node (ref "U5") (pin "5") (pinfunction "RX_5") (pintype "bidirectional"))
      (node (ref "U7") (pin "51") (pinfunction "PA20_51") (pintype "bidirectional"))
    )
    (net (code "23") (name "GPS_OUT_TX") (class "Default")
      (node (ref "J7") (pin "16") (pinfunction "16_16") (pintype "passive"))
      (node (ref "U5") (pin "4") (pinfunction "TX_4") (pintype "bidirectional"))
      (node (ref "U7") (pin "50") (pinfunction "PA19_50") (pintype "bidirectional"))
    )
    (net (code "24") (name "LINUX_ENABLE_POWER") (class "Default")
      (node (ref "Q1") (pin "D1") (pinfunction "D1_D1") (pintype "bidirectional"))
      (node (ref "R25") (pin "1") (pinfunction "1_1") (pintype "passive"))
      (node (ref "SW5") (pin "4") (pinfunction "EN_4") (pintype "bidirectional"))
    )
    (net (code "25") (name "MEMORY_MISO") (class "Default")
      (node (ref "J7") (pin "7") (pinfunction "7_7") (pintype "passive"))
      (node (ref "U1") (pin "2") (pinfunction "SO_2") (pintype "bidirectional"))
      (node (ref "U6") (pin "32") (pinfunction "PA12_32") (pintype "bidirectional"))
      (node (ref "U7") (pin "31") (pinfunction "PA11_31") (pintype "bidirectional"))
    )
    (net (code "26") (name "MEMORY_MOSI") (class "Default")
      (node (ref "J7") (pin "5") (pinfunction "5_5") (pintype "passive"))
      (node (ref "U1") (pin "5") (pinfunction "SI_5") (pintype "bidirectional"))
      (node (ref "U6") (pin "31") (pinfunction "PA11_31") (pintype "bidirectional"))
      (node (ref "U7") (pin "32") (pinfunction "PA12_32") (pintype "bidirectional"))
    )
    (net (code "27") (name "MEMORY_SCLK") (class "Default")
      (node (ref "J7") (pin "6") (pinfunction "6_6") (pintype "passive"))
      (node (ref "U1") (pin "6") (pinfunction "SCK_6") (pintype "bidirectional"))
      (node (ref "U6") (pin "30") (pinfunction "PA10_30") (pintype "bidirectional"))
      (node (ref "U7") (pin "30") (pinfunction "PA10_30") (pintype "bidirectional"))
    )
    (net (code "28") (name "MOD0_IN") (class "Default")
      (node (ref "J4") (pin "9") (pinfunction "MOD0_IN_9") (pintype "bidirectional"))
      (node (ref "U7") (pin "15") (pinfunction "PA04_15") (pintype "bidirectional"))
    )
    (net (code "29") (name "MOD0_OUT") (class "Default")
      (node (ref "J4") (pin "10") (pinfunction "MOD0_OUT_10") (pintype "bidirectional"))
      (node (ref "U7") (pin "40") (pinfunction "PA13_40") (pintype "bidirectional"))
    )
    (net (code "30") (name "MOD1_IN") (class "Default")
      (node (ref "J4") (pin "11") (pinfunction "MOD1_IN_11") (pintype "bidirectional"))
      (node (ref "U7") (pin "16") (pinfunction "PA05_16") (pintype "bidirectional"))
    )
    (net (code "31") (name "MOD1_OUT") (class "Default")
      (node (ref "J4") (pin "12") (pinfunction "MOD1_OUT_12") (pintype "bidirectional"))
      (node (ref "U7") (pin "41") (pinfunction "PA14_41") (pintype "bidirectional"))
    )
    (net (code "32") (name "MOD2_IN") (class "Default")
      (node (ref "J4") (pin "13") (pinfunction "MOD2_IN_13") (pintype "bidirectional"))
      (node (ref "U7") (pin "21") (pinfunction "PA06_21") (pintype "bidirectional"))
    )
    (net (code "33") (name "MOD2_OUT") (class "Default")
      (node (ref "J4") (pin "14") (pinfunction "MOD2_OUT_14") (pintype "bidirectional"))
      (node (ref "U7") (pin "42") (pinfunction "PA15_42") (pintype "bidirectional"))
    )
    (net (code "34") (name "MOD5_IN") (class "Default")
      (node (ref "J4") (pin "15") (pinfunction "MOD5_IN_15") (pintype "bidirectional"))
      (node (ref "U7") (pin "22") (pinfunction "PA07_22") (pintype "bidirectional"))
    )
    (net (code "35") (name "MOD5_OUT") (class "Default")
      (node (ref "J4") (pin "16") (pinfunction "MOD5_OUT_16") (pintype "bidirectional"))
      (node (ref "U7") (pin "43") (pinfunction "PA16_43") (pintype "bidirectional"))
    )
    (net (code "36") (name "MOD6_IN") (class "Default")
      (node (ref "J4") (pin "17") (pinfunction "MOD6_IN_17") (pintype "bidirectional"))
      (node (ref "U7") (pin "26") (pinfunction "PA08_26") (pintype "bidirectional"))
    )
    (net (code "37") (name "MOD6_OUT") (class "Default")
      (node (ref "J4") (pin "18") (pinfunction "MOD6_OUT_18") (pintype "bidirectional"))
      (node (ref "U7") (pin "44") (pinfunction "PA17_44") (pintype "bidirectional"))
    )
    (net (code "38") (name "MOD7_IN") (class "Default")
      (node (ref "J4") (pin "19") (pinfunction "MOD7_IN_19") (pintype "bidirectional"))
      (node (ref "U7") (pin "29") (pinfunction "PA09_29") (pintype "bidirectional"))
    )
    (net (code "39") (name "MOD7_OUT") (class "Default")
      (node (ref "J4") (pin "20") (pinfunction "MOD7_OUT_20") (pintype "bidirectional"))
      (node (ref "U7") (pin "49") (pinfunction "PA18_49") (pintype "bidirectional"))
    )
    (net (code "40") (name "MODSTORAGE_IN") (class "Default")
      (node (ref "U6") (pin "14") (pinfunction "PB03_14") (pintype "bidirectional"))
      (node (ref "U7") (pin "46") (pinfunction "PB09_46") (pintype "bidirectional"))
    )
    (net (code "41") (name "MODSTORAGE_OUT") (class "Default")
      (node (ref "U6") (pin "12") (pinfunction "PB01_12") (pintype "bidirectional"))
      (node (ref "U7") (pin "47") (pinfunction "PB10_47") (pintype "bidirectional"))
    )
    (net (code "42") (name "MODULES_SCL") (class "Default")
      (node (ref "J4") (pin "24") (pinfunction "MODULES_SCL_24") (pintype "bidirectional"))
      (node (ref "U10") (pin "14") (pinfunction "B6_14") (pintype "bidirectional"))
      (node (ref "U6") (pin "60") (pinfunction "PA24_60") (pintype "bidirectional"))
      (node (ref "U7") (pin "12") (pinfunction "PB01_12") (pintype "bidirectional"))
      (node (ref "U7") (pin "60") (pinfunction "PA24_60") (pintype "bidirectional"))
    )
    (net (code "43") (name "MODULES_SDA") (class "Default")
      (node (ref "J4") (pin "23") (pinfunction "MODULES_SDA_23") (pintype "bidirectional"))
      (node (ref "U10") (pin "15") (pinfunction "B5_15") (pintype "bidirectional"))
      (node (ref "U6") (pin "59") (pinfunction "PA23_59") (pintype "bidirectional"))
      (node (ref "U7") (pin "14") (pinfunction "PB03_14") (pintype "bidirectional"))
      (node (ref "U7") (pin "59") (pinfunction "PA23_59") (pintype "bidirectional"))
    )
    (net (code "44") (name "Net-(C28-1)") (class "Default")
      (node (ref "C28") (pin "P$1") (pinfunction "1_P$1") (pintype "bidirectional"))
      (node (ref "J10") (pin "2") (pinfunction "2_2") (pintype "passive"))
      (node (ref "VR1") (pin "1") (pinfunction "EN_1") (pintype "bidirectional"))
      (node (ref "VR1") (pin "7") (pinfunction "VIN_7") (pintype "bidirectional"))
    )
    (net (code "45") (name "Net-(D1-PadCATHODE)") (class "Default")
      (node (ref "D1") (pin "CATHODE") (pinfunction "CATHODE_CATHODE") (pintype "bidirectional"))
      (node (ref "J9") (pin "2") (pinfunction "2_2") (pintype "passive"))
    )
    (net (code "46") (name "Net-(D2-B)") (class "Default")
      (node (ref "D2") (pin "3") (pinfunction "B_3") (pintype "output"))
      (node (ref "R6") (pin "1") (pinfunction "1_1") (pintype "passive"))
    )
    (net (code "47") (name "Net-(D2-R)") (class "Default")
      (node (ref "D2") (pin "2") (pinfunction "R_2") (pintype "output"))
      (node (ref "R5") (pin "1") (pinfunction "1_1") (pintype "passive"))
    )
    (net (code "48") (name "Net-(D3-B)") (class "Default")
      (node (ref "D3") (pin "3") (pinfunction "B_3") (pintype "output"))
      (node (ref "R9") (pin "1") (pinfunction "1_1") (pintype "passive"))
    )
    (net (code "49") (name "Net-(D3-G)") (class "Default")
      (node (ref "D3") (pin "4") (pinfunction "G_4") (pintype "output"))
      (node (ref "R8") (pin "1") (pinfunction "1_1") (pintype "passive"))
    )
    (net (code "50") (name "Net-(D3-R)") (class "Default")
      (node (ref "D3") (pin "2") (pinfunction "R_2") (pintype "output"))
      (node (ref "R7") (pin "1") (pinfunction "1_1") (pintype "passive"))
    )
    (net (code "51") (name "Net-(E_1D-GP27_I2C_6_SCL)") (class "Default")
      (node (ref "E_1") (pin "45") (pinfunction "GP27_I2C_6_SCL_45") (pintype "bidirectional"))
      (node (ref "U10") (pin "7") (pinfunction "A6_7") (pintype "bidirectional"))
    )
    (net (code "52") (name "Net-(E_1D-GP28_I2C_6_SDA)") (class "Default")
      (node (ref "E_1") (pin "47") (pinfunction "GP28_I2C_6_SDA_47") (pintype "bidirectional"))
      (node (ref "U10") (pin "6") (pinfunction "A5_6") (pintype "bidirectional"))
    )
    (net (code "53") (name "Net-(E_1G-GP110_SPI_2_FS0)") (class "Default")
      (node (ref "E_1") (pin "53") (pinfunction "GP110_SPI_2_FS0_53") (pintype "bidirectional"))
      (node (ref "J13") (pin "1") (pinfunction "1_1") (pintype "passive"))
    )
    (net (code "54") (name "Net-(E_1G-GP111_SPI_2_FS1)") (class "Default")
      (node (ref "E_1") (pin "51") (pinfunction "GP111_SPI_2_FS1_51") (pintype "bidirectional"))
      (node (ref "J13") (pin "3") (pinfunction "3_3") (pintype "passive"))
    )
    (net (code "55") (name "Net-(E_1J-USB_DN)") (class "Default")
      (node (ref "E_1") (pin "18") (pinfunction "USB_DN_18") (pintype "bidirectional"))
      (node (ref "U9") (pin "5") (pinfunction "D-_5") (pintype "bidirectional"))
    )
    (net (code "56") (name "Net-(E_1J-USB_DP)") (class "Default")
      (node (ref "E_1") (pin "16") (pinfunction "USB_DP_16") (pintype "bidirectional"))
      (node (ref "U9") (pin "3") (pinfunction "D+_3") (pintype "bidirectional"))
    )
    (net (code "57") (name "Net-(E_1J-USB_ID)") (class "Default")
      (node (ref "E_1") (pin "3") (pinfunction "USB_ID_3") (pintype "bidirectional"))
      (node (ref "U8") (pin "4") (pinfunction "Y_4") (pintype "bidirectional"))
    )
    (net (code "58") (name "Net-(FB1-P$1)") (class "Default")
      (node (ref "FB1") (pin "1") (pinfunction "P$1_1") (pintype "bidirectional"))
      (node (ref "U5") (pin "17") (pinfunction "VOUT_17") (pintype "bidirectional"))
    )
    (net (code "59") (name "Net-(FB1-P$2)") (class "Default")
      (node (ref "FB1") (pin "2") (pinfunction "P$2_2") (pintype "bidirectional"))
      (node (ref "J16") (pin "SIG") (pinfunction "ANT_SIG") (pintype "bidirectional"))
      (node (ref "U5") (pin "19") (pinfunction "RFIN_19") (pintype "bidirectional"))
    )
    (net (code "60") (name "Net-(FB3-P$1)") (class "Default")
      (node (ref "C8") (pin "1") (pinfunction "1_1") (pintype "bidirectional"))
      (node (ref "FB3") (pin "1") (pinfunction "P$1_1") (pintype "bidirectional"))
      (node (ref "U6") (pin "25") (pinfunction "VDDANA_25") (pintype "power_in"))
    )
    (net (code "61") (name "Net-(FB4-P$1)") (class "Default")
      (node (ref "C13") (pin "1") (pinfunction "1_1") (pintype "bidirectional"))
      (node (ref "FB4") (pin "1") (pinfunction "P$1_1") (pintype "bidirectional"))
      (node (ref "U7") (pin "25") (pinfunction "VDDANA_25") (pintype "power_in"))
    )
    (net (code "62") (name "Net-(J1-VCC)") (class "Default")
      (node (ref "C27") (pin "1") (pinfunction "1_1") (pintype "bidirectional"))
      (node (ref "J1") (pin "4") (pinfunction "VCC_4") (pintype "bidirectional"))
      (node (ref "J12") (pin "2") (pinfunction "2_2") (pintype "passive"))
      (node (ref "R12") (pin "2") (pinfunction "2_2") (pintype "passive"))
      (node (ref "R13") (pin "2") (pinfunction "2_2") (pintype "passive"))
      (node (ref "R14") (pin "2") (pinfunction "2_2") (pintype "passive"))
      (node (ref "R20") (pin "2") (pinfunction "2_2") (pintype "passive"))
    )
    (net (code "63") (name "Net-(J2-+5V)") (class "Default")
      (node (ref "FB2") (pin "P$2") (pinfunction "P$2_P$2") (pintype "bidirectional"))
      (node (ref "J2") (pin "1") (pinfunction "+5V_1") (pintype "bidirectional"))
    )
    (net (code "64") (name "Net-(J2-D+)") (class "Default")
      (node (ref "C6") (pin "1") (pinfunction "1_1") (pintype "bidirectional"))
      (node (ref "J2") (pin "3") (pinfunction "D+_3") (pintype "bidirectional"))
      (node (ref "R2") (pin "1") (pinfunction "1_1") (pintype "passive"))
    )
    (net (code "65") (name "Net-(J2-D-)") (class "Default")
      (node (ref "C5") (pin "1") (pinfunction "1_1") (pintype "bidirectional"))
      (node (ref "J2") (pin "2") (pinfunction "D-_2") (pintype "bidirectional"))
      (node (ref "R1") (pin "1") (pinfunction "1_1") (pintype "passive"))
    )
    (net (code "66") (name "Net-(J3-D+)") (class "Default")
      (node (ref "J3") (pin "3") (pinfunction "D+_3") (pintype "bidirectional"))
      (node (ref "U9") (pin "1") (pinfunction "D1+_1") (pintype "bidirectional"))
    )
    (net (code "67") (name "Net-(J3-D-)") (class "Default")
      (node (ref "J3") (pin "2") (pinfunction "D-_2") (pintype "bidirectional"))
      (node (ref "U9") (pin "7") (pinfunction "D1-_7") (pintype "bidirectional"))
    )
    (net (code "68") (name "Net-(L1-1)") (class "Default")
      (node (ref "L1") (pin "P$1") (pinfunction "1_P$1") (pintype "bidirectional"))
      (node (ref "VR1") (pin "6") (pinfunction "SW_6") (pintype "bidirectional"))
    )
    (net (code "69") (name "Net-(L2-1)") (class "Default")
      (node (ref "C12") (pin "1") (pinfunction "1_1") (pintype "bidirectional"))
      (node (ref "C25") (pin "1") (pinfunction "1_1") (pintype "bidirectional"))
      (node (ref "L2") (pin "P$1") (pinfunction "1_P$1") (pintype "bidirectional"))
      (node (ref "U6") (pin "7") (pinfunction "VDDOUT_7") (pintype "power_in"))
    )
    (net (code "70") (name "Net-(L2-2)") (class "Default")
      (node (ref "L2") (pin "P$2") (pinfunction "2_P$2") (pintype "bidirectional"))
      (node (ref "U6") (pin "5") (pinfunction "VDDCORE_5") (pintype "power_in"))
    )
    (net (code "71") (name "Net-(L3-1)") (class "Default")
      (node (ref "C17") (pin "1") (pinfunction "1_1") (pintype "bidirectional"))
      (node (ref "C26") (pin "1") (pinfunction "1_1") (pintype "bidirectional"))
      (node (ref "L3") (pin "P$1") (pinfunction "1_P$1") (pintype "bidirectional"))
      (node (ref "U7") (pin "7") (pinfunction "VDDOUT_7") (pintype "power_in"))
    )
    (net (code "72") (name "Net-(L3-2)") (class "Default")
      (node (ref "L3") (pin "P$2") (pinfunction "2_P$2") (pintype "bidirectional"))
      (node (ref "U7") (pin "5") (pinfunction "VDDCORE_5") (pintype "power_in"))
    )
    (net (code "73") (name "Net-(SW5-VLOAD)") (class "Default")
      (node (ref "J10") (pin "1") (pinfunction "1_1") (pintype "passive"))
      (node (ref "SW5") (pin "1") (pinfunction "VLOAD_1") (pintype "bidirectional"))
    )
    (net (code "74") (name "Net-(SW6-VLOAD)") (class "Default")
      (node (ref "J11") (pin "1") (pinfunction "1_1") (pintype "passive"))
      (node (ref "SW6") (pin "1") (pinfunction "VLOAD_1") (pintype "bidirectional"))
    )
    (net (code "75") (name "Net-(SW7-VLOAD)") (class "Default")
      (node (ref "J12") (pin "1") (pinfunction "1_1") (pintype "passive"))
      (node (ref "SW7") (pin "1") (pinfunction "VLOAD_1") (pintype "bidirectional"))
    )
    (net (code "76") (name "Net-(U2-RXD)") (class "Default")
      (node (ref "R4") (pin "1") (pinfunction "1_1") (pintype "passive"))
      (node (ref "U2") (pin "10") (pinfunction "RXD_10") (pintype "bidirectional"))
    )
    (net (code "77") (name "Net-(U2-TXD)") (class "Default")
      (node (ref "R3") (pin "1") (pinfunction "1_1") (pintype "passive"))
      (node (ref "U2") (pin "7") (pinfunction "TXD_7") (pintype "bidirectional"))
    )
    (net (code "78") (name "Net-(U2-USBDM)") (class "Default")
      (node (ref "R1") (pin "2") (pinfunction "2_2") (pintype "passive"))
      (node (ref "U2") (pin "1") (pinfunction "USBDM_1") (pintype "bidirectional"))
    )
    (net (code "79") (name "Net-(U2-USBDP)") (class "Default")
      (node (ref "R2") (pin "2") (pinfunction "2_2") (pintype "passive"))
      (node (ref "U2") (pin "12") (pinfunction "USBDP_12") (pintype "bidirectional"))
    )
    (net (code "80") (name "Net-(U2-VCC)") (class "Default")
      (node (ref "C7") (pin "1") (pinfunction "1_1") (pintype "bidirectional"))
      (node (ref "FB2") (pin "P$1") (pinfunction "P$1_P$1") (pintype "bidirectional"))
      (node (ref "U2") (pin "4") (pinfunction "VCC_4") (pintype "bidirectional"))
    )
    (net (code "81") (name "Net-(U5-VBACKUP)") (class "Default")
      (node (ref "C18") (pin "1") (pinfunction "1_1") (pintype "bidirectional"))
      (node (ref "J11") (pin "2") (pinfunction "2_2") (pintype "passive"))
      (node (ref "U5") (pin "11") (pinfunction "VBACKUP_11") (pintype "bidirectional"))
      (node (ref "U5") (pin "12") (pinfunction "VCC_12") (pintype "bidirectional"))
    )
    (net (code "82") (name "Net-(U6-BIASH)") (class "Default")
      (node (ref "U6") (pin "36") (pinfunction "BIASH_36") (pintype "bidirectional"))
      (node (ref "U6") (pin "37") (pinfunction "BIASL_37") (pintype "bidirectional"))
    )
    (net (code "83") (name "Net-(U6-CAPH)") (class "Default")
      (node (ref "U6") (pin "33") (pinfunction "CAPH_33") (pintype "bidirectional"))
      (node (ref "U6") (pin "34") (pinfunction "CAPL_34") (pintype "bidirectional"))
    )
    (net (code "84") (name "Net-(U6-PA02)") (class "Default")
      (node (ref "R10") (pin "1") (pinfunction "1_1") (pintype "passive"))
      (node (ref "R27") (pin "2") (pinfunction "2_2") (pintype "passive"))
      (node (ref "U6") (pin "3") (pinfunction "PA02_3") (pintype "bidirectional"))
    )
    (net (code "85") (name "Net-(U7-BIASH)") (class "Default")
      (node (ref "U7") (pin "36") (pinfunction "BIASH_36") (pintype "bidirectional"))
      (node (ref "U7") (pin "37") (pinfunction "BIASL_37") (pintype "bidirectional"))
    )
    (net (code "86") (name "Net-(U7-CAPH)") (class "Default")
      (node (ref "U7") (pin "33") (pinfunction "CAPH_33") (pintype "bidirectional"))
      (node (ref "U7") (pin "34") (pinfunction "CAPL_34") (pintype "bidirectional"))
    )
    (net (code "87") (name "Net-(U7-PA02)") (class "Default")
      (node (ref "R11") (pin "1") (pinfunction "1_1") (pintype "passive"))
      (node (ref "R26") (pin "2") (pinfunction "2_2") (pintype "passive"))
      (node (ref "U7") (pin "3") (pinfunction "PA02_3") (pintype "bidirectional"))
    )
    (net (code "88") (name "Net-(U9-S)") (class "Default")
      (node (ref "Q1") (pin "D2") (pinfunction "D2_D2") (pintype "bidirectional"))
      (node (ref "R22") (pin "2") (pinfunction "2_2") (pintype "passive"))
      (node (ref "U9") (pin "10") (pinfunction "S_10") (pintype "bidirectional"))
    )
    (net (code "89") (name "Net-(U10-B7)") (class "Default")
      (node (ref "R6") (pin "2") (pinfunction "2_2") (pintype "passive"))
      (node (ref "U10") (pin "13") (pinfunction "B7_13") (pintype "bidirectional"))
    )
    (net (code "90") (name "PPS") (class "Default")
      (node (ref "J4") (pin "25") (pinfunction "PPS_25") (pintype "bidirectional"))
      (node (ref "U5") (pin "3") (pinfunction "1PPS_3") (pintype "bidirectional"))
      (node (ref "U7") (pin "45") (pinfunction "PB08_45") (pintype "bidirectional"))
    )
    (net (code "91") (name "SD_ENABLE_POWER") (class "Default")
      (node (ref "R24") (pin "1") (pinfunction "1_1") (pintype "passive"))
      (node (ref "SW7") (pin "4") (pinfunction "EN_4") (pintype "bidirectional"))
      (node (ref "U6") (pin "55") (pinfunction "PA21_55") (pintype "bidirectional"))
    )
    (net (code "92") (name "SD_MISO") (class "Default")
      (node (ref "J1") (pin "7") (pinfunction "DATA0/MISO_7") (pintype "bidirectional"))
      (node (ref "J7") (pin "2") (pinfunction "2_2") (pintype "passive"))
      (node (ref "R14") (pin "1") (pinfunction "1_1") (pintype "passive"))
      (node (ref "U6") (pin "42") (pinfunction "PA15_42") (pintype "bidirectional"))
    )
    (net (code "93") (name "SD_MOSI") (class "Default")
      (node (ref "J1") (pin "3") (pinfunction "CMD/MOSI_3") (pintype "bidirectional"))
      (node (ref "J7") (pin "1") (pinfunction "1_1") (pintype "passive"))
      (node (ref "R12") (pin "1") (pinfunction "1_1") (pintype "passive"))
      (node (ref "U6") (pin "43") (pinfunction "PA16_43") (pintype "bidirectional"))
    )
    (net (code "94") (name "SD_SCLK") (class "Default")
      (node (ref "J1") (pin "5") (pinfunction "CLK_5") (pintype "bidirectional"))
      (node (ref "J7") (pin "3") (pinfunction "3_3") (pintype "passive"))
      (node (ref "U6") (pin "41") (pinfunction "PA14_41") (pintype "bidirectional"))
    )
    (net (code "95") (name "SMBCLK") (class "Default")
      (node (ref "J4") (pin "5") (pinfunction "SMBCLK_5") (pintype "bidirectional"))
      (node (ref "U7") (pin "56") (pinfunction "PA22_56") (pintype "bidirectional"))
    )
    (net (code "96") (name "SMBDATA") (class "Default")
      (node (ref "J4") (pin "3") (pinfunction "SMBDATA_3") (pintype "bidirectional"))
      (node (ref "U7") (pin "55") (pinfunction "PA21_55") (pintype "bidirectional"))
    )
    (net (code "97") (name "STORAGE_DEBUG_GPIO1") (class "Default")
      (node (ref "J4") (pin "201") (pinfunction "DBG_GPIO1_201") (pintype "bidirectional"))
      (node (ref "U6") (pin "19") (pinfunction "PB04_19") (pintype "bidirectional"))
    )
    (net (code "98") (name "STORAGE_DEBUG_GPIO2") (class "Default")
      (node (ref "J4") (pin "204") (pinfunction "DBG_GPIO2_204") (pintype "bidirectional"))
      (node (ref "U6") (pin "20") (pinfunction "PB05_20") (pintype "bidirectional"))
    )
    (net (code "99") (name "STORAGE_DEBUG_RX") (class "Default")
      (node (ref "J4") (pin "203") (pinfunction "DBG_RX_203") (pintype "bidirectional"))
      (node (ref "U6") (pin "46") (pinfunction "PB09_46") (pintype "bidirectional"))
    )
    (net (code "100") (name "STORAGE_DEBUG_TX") (class "Default")
      (node (ref "J4") (pin "202") (pinfunction "DBG_TX_202") (pintype "bidirectional"))
      (node (ref "U6") (pin "47") (pinfunction "PB10_47") (pintype "bidirectional"))
    )
    (net (code "101") (name "STORAGE_INTERRUPT") (class "Default")
      (node (ref "U6") (pin "26") (pinfunction "PA08_26") (pintype "bidirectional"))
      (node (ref "U7") (pin "53") (pinfunction "PB12_53") (pintype "bidirectional"))
    )
    (net (code "102") (name "STORAGE_SWDCLK") (class "Default")
      (node (ref "J14") (pin "4") (pinfunction "SWDCLK_4") (pintype "bidirectional"))
      (node (ref "J4") (pin "206") (pinfunction "DBG_SWDCLK_206") (pintype "bidirectional"))
      (node (ref "R17") (pin "1") (pinfunction "1_1") (pintype "passive"))
      (node (ref "U6") (pin "9") (pinfunction "TCK_9") (pintype "bidirectional"))
    )
    (net (code "103") (name "STORAGE_SWDIO") (class "Default")
      (node (ref "J14") (pin "2") (pinfunction "SWDIO_2") (pintype "bidirectional"))
      (node (ref "J4") (pin "207") (pinfunction "DBG_SWDIO_207") (pintype "bidirectional"))
      (node (ref "R16") (pin "1") (pinfunction "1_1") (pintype "passive"))
      (node (ref "U6") (pin "10") (pinfunction "PA03_10") (pintype "bidirectional"))
    )
    (net (code "104") (name "STORAGE_XIN") (class "Default")
      (node (ref "C1") (pin "1") (pinfunction "1_1") (pintype "bidirectional"))
      (node (ref "U6") (pin "1") (pinfunction "PA00_1") (pintype "bidirectional"))
      (node (ref "X1") (pin "3") (pinfunction "2_3") (pintype "bidirectional"))
    )
    (net (code "105") (name "STORAGE_XOUT") (class "Default")
      (node (ref "C2") (pin "1") (pinfunction "1_1") (pintype "bidirectional"))
      (node (ref "U6") (pin "2") (pinfunction "PA01_2") (pintype "bidirectional"))
      (node (ref "X1") (pin "1") (pinfunction "1_1") (pintype "bidirectional"))
    )
    (net (code "106") (name "USB_MOD_D+") (class "Default")
      (node (ref "J4") (pin "27") (pinfunction "USB_D+_27") (pintype "bidirectional"))
      (node (ref "U9") (pin "2") (pinfunction "D2+_2") (pintype "bidirectional"))
    )
    (net (code "107") (name "USB_MOD_D-") (class "Default")
      (node (ref "J4") (pin "28") (pinfunction "USB_D-_28") (pintype "bidirectional"))
      (node (ref "U9") (pin "6") (pinfunction "D2-_6") (pintype "bidirectional"))
    )
    (net (code "108") (name "USB_VBUS") (class "Default")
      (node (ref "D1") (pin "ANODE") (pinfunction "ANODE_ANODE") (pintype "bidirectional"))
      (node (ref "E_1") (pin "20") (pinfunction "USB_VBUS_20") (pintype "bidirectional"))
      (node (ref "J3") (pin "1") (pinfunction "+5V_1") (pintype "bidirectional"))
      (node (ref "Q1") (pin "G2") (pinfunction "G2_G2") (pintype "input"))
      (node (ref "R21") (pin "1") (pinfunction "1_1") (pintype "passive"))
      (node (ref "U8") (pin "1") (pinfunction "~{OE}_1") (pintype "bidirectional"))
    )
    (net (code "109") (name "VCC_CONTROLLER") (class "Default")
      (node (ref "C10") (pin "1") (pinfunction "1_1") (pintype "bidirectional"))
      (node (ref "C11") (pin "1") (pinfunction "1_1") (pintype "bidirectional"))
      (node (ref "C14") (pin "1") (pinfunction "1_1") (pintype "bidirectional"))
      (node (ref "C15") (pin "1") (pinfunction "1_1") (pintype "bidirectional"))
      (node (ref "C16") (pin "1") (pinfunction "1_1") (pintype "bidirectional"))
      (node (ref "C19") (pin "1") (pinfunction "1_1") (pintype "bidirectional"))
      (node (ref "C29") (pin "1") (pinfunction "1_1") (pintype "bidirectional"))
      (node (ref "C9") (pin "1") (pinfunction "1_1") (pintype "bidirectional"))
      (node (ref "D3") (pin "1") (pinfunction "VDD_1") (pintype "bidirectional"))
      (node (ref "FB3") (pin "2") (pinfunction "P$2_2") (pintype "bidirectional"))
      (node (ref "FB4") (pin "2") (pinfunction "P$2_2") (pintype "bidirectional"))
      (node (ref "J14") (pin "1") (pinfunction "VCC_1") (pintype "bidirectional"))
      (node (ref "J15") (pin "1") (pinfunction "VCC_1") (pintype "bidirectional"))
      (node (ref "J4") (pin "2") (pinfunction "VCC_CONTROLLER_2") (pintype "bidirectional"))
      (node (ref "J7") (pin "20") (pinfunction "20_20") (pintype "passive"))
      (node (ref "R10") (pin "2") (pinfunction "2_2") (pintype "passive"))
      (node (ref "R11") (pin "2") (pinfunction "2_2") (pintype "passive"))
      (node (ref "R16") (pin "2") (pinfunction "2_2") (pintype "passive"))
      (node (ref "R17") (pin "2") (pinfunction "2_2") (pintype "passive"))
      (node (ref "R18") (pin "2") (pinfunction "2_2") (pintype "passive"))
      (node (ref "R19") (pin "2") (pinfunction "2_2") (pintype "passive"))
      (node (ref "R23") (pin "2") (pinfunction "2_2") (pintype "passive"))
      (node (ref "R24") (pin "2") (pinfunction "2_2") (pintype "passive"))
      (node (ref "SW6") (pin "3") (pinfunction "VSUPP_3") (pintype "bidirectional"))
      (node (ref "SW7") (pin "3") (pinfunction "VSUPP_3") (pintype "bidirectional"))
      (node (ref "U1") (pin "3") (pinfunction "~{WP}_3") (pintype "bidirectional"))
      (node (ref "U1") (pin "7") (pinfunction "~{HOLD}_7") (pintype "bidirectional"))
      (node (ref "U1") (pin "8") (pinfunction "VDD_8") (pintype "bidirectional"))
      (node (ref "U3") (pin "2") (pinfunction "VCC_2") (pintype "bidirectional"))
      (node (ref "U4") (pin "2") (pinfunction "VCC_2") (pintype "bidirectional"))
      (node (ref "U6") (pin "35") (pinfunction "VLCD_35") (pintype "bidirectional"))
      (node (ref "U6") (pin "39") (pinfunction "VLCDIN_39") (pintype "power_in"))
      (node (ref "U6") (pin "52") (pinfunction "VDDIO_52") (pintype "power_in"))
      (node (ref "U6") (pin "61") (pinfunction "VDDIO_61") (pintype "power_in"))
      (node (ref "U6") (pin "8") (pinfunction "VDDIN_8") (pintype "power_in"))
      (node (ref "U7") (pin "35") (pinfunction "VLCD_35") (pintype "bidirectional"))
      (node (ref "U7") (pin "39") (pinfunction "VLCDIN_39") (pintype "power_in"))
      (node (ref "U7") (pin "52") (pinfunction "VDDIO_52") (pintype "power_in"))
      (node (ref "U7") (pin "61") (pinfunction "VDDIO_61") (pintype "power_in"))
      (node (ref "U7") (pin "8") (pinfunction "VDDIN_8") (pintype "power_in"))
    )
    (net (code "110") (name "VCC_LINUX") (class "Default")
      (node (ref "J4") (pin "4") (pinfunction "VCC_LINUX_4") (pintype "bidirectional"))
      (node (ref "J7") (pin "17") (pinfunction "17_17") (pintype "passive"))
      (node (ref "J9") (pin "1") (pinfunction "1_1") (pintype "passive"))
      (node (ref "R25") (pin "2") (pinfunction "2_2") (pintype "passive"))
      (node (ref "SW5") (pin "3") (pinfunction "VSUPP_3") (pintype "bidirectional"))
      (node (ref "U8") (pin "5") (pinfunction "VCC_5") (pintype "power_in"))
    )
    (net (code "111") (name "VCC_LINUX_1V8") (class "Default")
      (node (ref "C23") (pin "1") (pinfunction "1_1") (pintype "bidirectional"))
      (node (ref "C24") (pin "2") (pinfunction "2_2") (pintype "bidirectional"))
      (node (ref "E_1") (pin "12") (pinfunction "1.8V_12") (pintype "bidirectional"))
      (node (ref "J7") (pin "14") (pinfunction "14_14") (pintype "passive"))
      (node (ref "U10") (pin "10") (pinfunction "OE_10") (pintype "bidirectional"))
      (node (ref "U10") (pin "2") (pinfunction "VCCA_2") (pintype "bidirectional"))
      (node (ref "U2") (pin "9") (pinfunction "VCCIO_9") (pintype "bidirectional"))
    )
    (net (code "112") (name "VCC_LINUX_3V3") (class "Default")
      (node (ref "C20") (pin "1") (pinfunction "1_1") (pintype "bidirectional"))
      (node (ref "C21") (pin "2") (pinfunction "2_2") (pintype "bidirectional"))
      (node (ref "C22") (pin "1") (pinfunction "1_1") (pintype "bidirectional"))
      (node (ref "C30") (pin "P$1") (pinfunction "1_P$1") (pintype "bidirectional"))
      (node (ref "D2") (pin "1") (pinfunction "VDD_1") (pintype "bidirectional"))
      (node (ref "E_1") (pin "14") (pinfunction "DCIN_14") (pintype "bidirectional"))
      (node (ref "E_1") (pin "2") (pinfunction "VSYS_2") (pintype "bidirectional"))
      (node (ref "E_1") (pin "4") (pinfunction "VSYS_4") (pintype "bidirectional"))
      (node (ref "E_1") (pin "6") (pinfunction "VSYS_6") (pintype "bidirectional"))
      (node (ref "J7") (pin "18") (pinfunction "18_18") (pintype "passive"))
      (node (ref "L1") (pin "P$2") (pinfunction "2_P$2") (pintype "bidirectional"))
      (node (ref "R15") (pin "2") (pinfunction "2_2") (pintype "passive"))
      (node (ref "R22") (pin "1") (pinfunction "1_1") (pintype "passive"))
      (node (ref "U10") (pin "19") (pinfunction "VCCB_19") (pintype "bidirectional"))
      (node (ref "U9") (pin "9") (pinfunction "VCC_9") (pintype "bidirectional"))
      (node (ref "VR1") (pin "3") (pinfunction "FB_3") (pintype "bidirectional"))
      (node (ref "VR1") (pin "4") (pinfunction "VOS_4") (pintype "bidirectional"))
    )
    (net (code "113") (name "unconnected-(D2-G-Pad4)") (class "Default")
      (node (ref "D2") (pin "4") (pinfunction "G_4") (pintype "output"))
    )
    (net (code "114") (name "unconnected-(E_1A-3.3V-Pad8)") (class "Default")
      (node (ref "E_1") (pin "8") (pinfunction "3.3V_8") (pintype "bidirectional"))
    )
    (net (code "115") (name "unconnected-(E_1A-3.3V-Pad10)") (class "Default")
      (node (ref "E_1") (pin "10") (pinfunction "3.3V_10") (pintype "bidirectional"))
    )
    (net (code "116") (name "unconnected-(E_1A-FW_RCVR-Pad69)") (class "Default")
      (node (ref "E_1") (pin "69") (pinfunction "FW_RCVR_69") (pintype "bidirectional"))
    )
    (net (code "117") (name "unconnected-(E_1A-MSIC_SLP_CLK-Pad7)") (class "Default")
      (node (ref "E_1") (pin "7") (pinfunction "MSIC_SLP_CLK_7") (pintype "bidirectional"))
    )
    (net (code "118") (name "unconnected-(E_1A-OSC_CLK_OUT_0-Pad67)") (class "Default")
      (node (ref "E_1") (pin "67") (pinfunction "OSC_CLK_OUT_0_67") (pintype "bidirectional"))
    )
    (net (code "119") (name "unconnected-(E_1A-RCVR_MODE-Pad31)") (class "Default")
      (node (ref "E_1") (pin "31") (pinfunction "RCVR_MODE_31") (pintype "bidirectional"))
    )
    (net (code "120") (name "unconnected-(E_1A-RESET_OUT#-Pad36)") (class "Default")
      (node (ref "E_1") (pin "36") (pinfunction "RESET_OUT#_36") (pintype "bidirectional"))
    )
    (net (code "121") (name "unconnected-(E_1A-V_VAT_BKUP-Pad23)") (class "Default")
      (node (ref "E_1") (pin "23") (pinfunction "V_VAT_BKUP_23") (pintype "bidirectional"))
    )
    (net (code "122") (name "unconnected-(E_1B-GP13_PWM1-Pad33)") (class "Default")
      (node (ref "E_1") (pin "33") (pinfunction "GP13_PWM1_33") (pintype "bidirectional"))
    )
    (net (code "123") (name "unconnected-(E_1B-GP14-Pad48)") (class "Default")
      (node (ref "E_1") (pin "48") (pinfunction "GP14_48") (pintype "bidirectional"))
    )
    (net (code "124") (name "unconnected-(E_1B-GP15-Pad42)") (class "Default")
      (node (ref "E_1") (pin "42") (pinfunction "GP15_42") (pintype "bidirectional"))
    )
    (net (code "125") (name "unconnected-(E_1B-GP44-Pad24)") (class "Default")
      (node (ref "E_1") (pin "24") (pinfunction "GP44_24") (pintype "bidirectional"))
    )
    (net (code "126") (name "unconnected-(E_1B-GP45-Pad26)") (class "Default")
      (node (ref "E_1") (pin "26") (pinfunction "GP45_26") (pintype "bidirectional"))
    )
    (net (code "127") (name "unconnected-(E_1B-GP46-Pad28)") (class "Default")
      (node (ref "E_1") (pin "28") (pinfunction "GP46_28") (pintype "bidirectional"))
    )
    (net (code "128") (name "unconnected-(E_1B-GP47-Pad30)") (class "Default")
      (node (ref "E_1") (pin "30") (pinfunction "GP47_30") (pintype "bidirectional"))
    )
    (net (code "129") (name "unconnected-(E_1B-GP48-Pad32)") (class "Default")
      (node (ref "E_1") (pin "32") (pinfunction "GP48_32") (pintype "bidirectional"))
    )
    (net (code "130") (name "unconnected-(E_1B-GP49-Pad34)") (class "Default")
      (node (ref "E_1") (pin "34") (pinfunction "GP49_34") (pintype "bidirectional"))
    )
    (net (code "131") (name "unconnected-(E_1B-GP165-Pad25)") (class "Default")
      (node (ref "E_1") (pin "25") (pinfunction "GP165_25") (pintype "bidirectional"))
    )
    (net (code "132") (name "unconnected-(E_1B-GP183_PWM3-Pad39)") (class "Default")
      (node (ref "E_1") (pin "39") (pinfunction "GP183_PWM3_39") (pintype "bidirectional"))
    )
    (net (code "133") (name "unconnected-(E_1C-GP19_I2C_1_SCL-Pad41)") (class "Default")
      (node (ref "E_1") (pin "41") (pinfunction "GP19_I2C_1_SCL_41") (pintype "bidirectional"))
    )
    (net (code "134") (name "unconnected-(E_1C-GP20_I2C_1_SDA-Pad43)") (class "Default")
      (node (ref "E_1") (pin "43") (pinfunction "GP20_I2C_1_SDA_43") (pintype "bidirectional"))
    )
    (net (code "135") (name "unconnected-(E_1E-GP40_I2S_2_CLK-Pad52)") (class "Default")
      (node (ref "E_1") (pin "52") (pinfunction "GP40_I2S_2_CLK_52") (pintype "bidirectional"))
    )
    (net (code "136") (name "unconnected-(E_1E-GP41_I2S_2_FS-Pad54)") (class "Default")
      (node (ref "E_1") (pin "54") (pinfunction "GP41_I2S_2_FS_54") (pintype "bidirectional"))
    )
    (net (code "137") (name "unconnected-(E_1E-GP42_I2S_2_RXD-Pad50)") (class "Default")
      (node (ref "E_1") (pin "50") (pinfunction "GP42_I2S_2_RXD_50") (pintype "bidirectional"))
    )
    (net (code "138") (name "unconnected-(E_1E-GP43_I2S_2_TXD-Pad56)") (class "Default")
      (node (ref "E_1") (pin "56") (pinfunction "GP43_I2S_2_TXD_56") (pintype "bidirectional"))
    )
    (net (code "139") (name "unconnected-(E_1F-GP77_SD_0_CD#-Pad60)") (class "Default")
      (node (ref "E_1") (pin "60") (pinfunction "GP77_SD_0_CD#_60") (pintype "bidirectional"))
    )
    (net (code "140") (name "unconnected-(E_1F-GP78_SD_0_CLK-Pad58)") (class "Default")
      (node (ref "E_1") (pin "58") (pinfunction "GP78_SD_0_CLK_58") (pintype "bidirectional"))
    )
    (net (code "141") (name "unconnected-(E_1F-GP79_SD_0_CMD-Pad62)") (class "Default")
      (node (ref "E_1") (pin "62") (pinfunction "GP79_SD_0_CMD_62") (pintype "bidirectional"))
    )
    (net (code "142") (name "unconnected-(E_1F-GP80_SD_0_DAT0-Pad66)") (class "Default")
      (node (ref "E_1") (pin "66") (pinfunction "GP80_SD_0_DAT0_66") (pintype "bidirectional"))
    )
    (net (code "143") (name "unconnected-(E_1F-GP81_SD_0_DAT1-Pad70)") (class "Default")
      (node (ref "E_1") (pin "70") (pinfunction "GP81_SD_0_DAT1_70") (pintype "bidirectional"))
    )
    (net (code "144") (name "unconnected-(E_1F-GP82_SD_0_DAT2-Pad64)") (class "Default")
      (node (ref "E_1") (pin "64") (pinfunction "GP82_SD_0_DAT2_64") (pintype "bidirectional"))
    )
    (net (code "145") (name "unconnected-(E_1F-GP83_SD_0_DAT3-Pad68)") (class "Default")
      (node (ref "E_1") (pin "68") (pinfunction "GP83_SD_0_DAT3_68") (pintype "bidirectional"))
    )
    (net (code "146") (name "unconnected-(E_1F-GP84_SD_0_CLK_FB-Pad44)") (class "Default")
      (node (ref "E_1") (pin "44") (pinfunction "GP84_SD_0_CLK_FB_44") (pintype "bidirectional"))
    )
    (net (code "147") (name "unconnected-(E_1H-GP128_UART_1_CTS-Pad65)") (class "Default")
      (node (ref "E_1") (pin "65") (pinfunction "GP128_UART_1_CTS_65") (pintype "bidirectional"))
    )
    (net (code "148") (name "unconnected-(E_1H-GP129_UART_1_RTS-Pad63)") (class "Default")
      (node (ref "E_1") (pin "63") (pinfunction "GP129_UART_1_RTS_63") (pintype "bidirectional"))
    )
    (net (code "149") (name "unconnected-(E_1H-GP130_UART_1_RX-Pad61)") (class "Default")
      (node (ref "E_1") (pin "61") (pinfunction "GP130_UART_1_RX_61") (pintype "bidirectional"))
    )
    (net (code "150") (name "unconnected-(E_1H-GP131_UART_1_TX-Pad46)") (class "Default")
      (node (ref "E_1") (pin "46") (pinfunction "GP131_UART_1_TX_46") (pintype "bidirectional"))
    )
    (net (code "151") (name "unconnected-(E_1J-FAULT-Pad19)") (class "Default")
      (node (ref "E_1") (pin "19") (pinfunction "FAULT_19") (pintype "bidirectional"))
    )
    (net (code "152") (name "unconnected-(E_1J-PSW-Pad21)") (class "Default")
      (node (ref "E_1") (pin "21") (pinfunction "PSW_21") (pintype "bidirectional"))
    )
    (net (code "153") (name "unconnected-(J1-DATA1{slash}RSV-Pad8)") (class "Default")
      (node (ref "J1") (pin "8") (pinfunction "DATA1/RSV_8") (pintype "bidirectional"))
    )
    (net (code "154") (name "unconnected-(J1-DATA2{slash}NC-Pad1)") (class "Default")
      (node (ref "J1") (pin "1") (pinfunction "DATA2/NC_1") (pintype "bidirectional"))
    )
    (net (code "155") (name "unconnected-(J2-ID-Pad4)") (class "Default")
      (node (ref "J2") (pin "4") (pinfunction "ID_4") (pintype "bidirectional"))
    )
    (net (code "156") (name "unconnected-(J3-ID-Pad4)") (class "Default")
      (node (ref "J3") (pin "4") (pinfunction "ID_4") (pintype "bidirectional"))
    )
    (net (code "157") (name "unconnected-(J14-SWO-Pad6)") (class "Default")
      (node (ref "J14") (pin "6") (pinfunction "SWO_6") (pintype "bidirectional"))
    )
    (net (code "158") (name "unconnected-(J15-SWO-Pad6)") (class "Default")
      (node (ref "J15") (pin "6") (pinfunction "SWO_6") (pintype "bidirectional"))
    )
    (net (code "159") (name "unconnected-(U2-3V3OUT-Pad3)") (class "Default")
      (node (ref "U2") (pin "3") (pinfunction "3V3OUT_3") (pintype "bidirectional"))
    )
    (net (code "160") (name "unconnected-(U2-CBUS0-Pad6)") (class "Default")
      (node (ref "U2") (pin "6") (pinfunction "CBUS0_6") (pintype "bidirectional"))
    )
    (net (code "161") (name "unconnected-(U2-~{CTS}-Pad11)") (class "Default")
      (node (ref "U2") (pin "11") (pinfunction "~{CTS}_11") (pintype "bidirectional"))
    )
    (net (code "162") (name "unconnected-(U2-~{RESET}-Pad2)") (class "Default")
      (node (ref "U2") (pin "2") (pinfunction "~{RESET}_2") (pintype "bidirectional"))
    )
    (net (code "163") (name "unconnected-(U2-~{RTS}-Pad8)") (class "Default")
      (node (ref "U2") (pin "8") (pinfunction "~{RTS}_8") (pintype "bidirectional"))
    )
    (net (code "164") (name "unconnected-(U5-~{RESET}-Pad8)") (class "Default")
      (node (ref "U5") (pin "8") (pinfunction "~{RESET}_8") (pintype "bidirectional"))
    )
    (net (code "165") (name "unconnected-(U6-ADVREFP-Pad24)") (class "Default")
      (node (ref "U6") (pin "24") (pinfunction "ADVREFP_24") (pintype "bidirectional"))
    )
    (net (code "166") (name "unconnected-(U6-PA04-Pad15)") (class "Default")
      (node (ref "U6") (pin "15") (pinfunction "PA04_15") (pintype "bidirectional"))
    )
    (net (code "167") (name "unconnected-(U6-PA25-Pad62)") (class "Default")
      (node (ref "U6") (pin "62") (pinfunction "PA25_62") (pintype "bidirectional"))
    )
    (net (code "168") (name "unconnected-(U6-PA26-Pad63)") (class "Default")
      (node (ref "U6") (pin "63") (pinfunction "PA26_63") (pintype "bidirectional"))
    )
    (net (code "169") (name "unconnected-(U6-PB00-Pad11)") (class "Default")
      (node (ref "U6") (pin "11") (pinfunction "PB00_11") (pintype "bidirectional"))
    )
    (net (code "170") (name "unconnected-(U6-PB02-Pad13)") (class "Default")
      (node (ref "U6") (pin "13") (pinfunction "PB02_13") (pintype "bidirectional"))
    )
    (net (code "171") (name "unconnected-(U6-PB06-Pad27)") (class "Default")
      (node (ref "U6") (pin "27") (pinfunction "PB06_27") (pintype "bidirectional"))
    )
    (net (code "172") (name "unconnected-(U6-PB07-Pad28)") (class "Default")
      (node (ref "U6") (pin "28") (pinfunction "PB07_28") (pintype "bidirectional"))
    )
    (net (code "173") (name "unconnected-(U6-PB08-Pad45)") (class "Default")
      (node (ref "U6") (pin "45") (pinfunction "PB08_45") (pintype "bidirectional"))
    )
    (net (code "174") (name "unconnected-(U6-PB11-Pad48)") (class "Default")
      (node (ref "U6") (pin "48") (pinfunction "PB11_48") (pintype "bidirectional"))
    )
    (net (code "175") (name "unconnected-(U6-PB12-Pad53)") (class "Default")
      (node (ref "U6") (pin "53") (pinfunction "PB12_53") (pintype "bidirectional"))
    )
    (net (code "176") (name "unconnected-(U6-PB13-Pad54)") (class "Default")
      (node (ref "U6") (pin "54") (pinfunction "PB13_54") (pintype "bidirectional"))
    )
    (net (code "177") (name "unconnected-(U6-XIN32-Pad17)") (class "Default")
      (node (ref "U6") (pin "17") (pinfunction "XIN32_17") (pintype "bidirectional"))
    )
    (net (code "178") (name "unconnected-(U6-XOUT32-Pad18)") (class "Default")
      (node (ref "U6") (pin "18") (pinfunction "XOUT32_18") (pintype "bidirectional"))
    )
    (net (code "179") (name "unconnected-(U7-ADVREFP-Pad24)") (class "Default")
      (node (ref "U7") (pin "24") (pinfunction "ADVREFP_24") (pintype "bidirectional"))
    )
    (net (code "180") (name "unconnected-(U7-PB00-Pad11)") (class "Default")
      (node (ref "U7") (pin "11") (pinfunction "PB00_11") (pintype "bidirectional"))
    )
    (net (code "181") (name "unconnected-(U7-PB02-Pad13)") (class "Default")
      (node (ref "U7") (pin "13") (pinfunction "PB02_13") (pintype "bidirectional"))
    )
    (net (code "182") (name "unconnected-(U7-XIN32-Pad17)") (class "Default")
      (node (ref "U7") (pin "17") (pinfunction "XIN32_17") (pintype "bidirectional"))
    )
    (net (code "183") (name "unconnected-(U7-XOUT32-Pad18)") (class "Default")
      (node (ref "U7") (pin "18") (pinfunction "XOUT32_18") (pintype "bidirectional"))
    )
    (net (code "184") (name "unconnected-(VR1-PG-Pad2)") (class "Default")
      (node (ref "VR1") (pin "2") (pinfunction "PG_2") (pintype "bidirectional"))
    )
    (net (code "185") (name "~{BACKPLANE_RESET}") (class "Default")
      (node (ref "J4") (pin "22") (pinfunction "~{BACKPLANE_RESET}_22") (pintype "bidirectional"))
      (node (ref "SW2") (pin "1") (pinfunction "P$1_1") (pintype "passive"))
      (node (ref "U6") (pin "58") (pinfunction "PB15_58") (pintype "bidirectional"))
    )
    (net (code "186") (name "~{CONTROLLER_LED}") (class "Default")
      (node (ref "R9") (pin "2") (pinfunction "2_2") (pintype "passive"))
      (node (ref "U7") (pin "48") (pinfunction "PB11_48") (pintype "bidirectional"))
    )
    (net (code "187") (name "~{CONTROLLER_RESET}") (class "Default")
      (node (ref "J15") (pin "3") (pinfunction "~{RESET}_3") (pintype "bidirectional"))
      (node (ref "J4") (pin "105") (pinfunction "DBG_~{RESET}_105") (pintype "bidirectional"))
      (node (ref "SW3") (pin "1") (pinfunction "P$1_1") (pintype "passive"))
      (node (ref "U3") (pin "1") (pinfunction "~{RST}_1") (pintype "bidirectional"))
      (node (ref "U7") (pin "4") (pinfunction "~{RESET}_4") (pintype "bidirectional"))
    )
    (net (code "188") (name "~{EDISON_PWRBTN}") (class "Default")
      (node (ref "E_1") (pin "17") (pinfunction "PWRBTN#_17") (pintype "bidirectional"))
      (node (ref "J8") (pin "2") (pinfunction "2_2") (pintype "passive"))
      (node (ref "R15") (pin "1") (pinfunction "1_1") (pintype "passive"))
      (node (ref "SW1") (pin "1") (pinfunction "P$1_1") (pintype "passive"))
      (node (ref "U6") (pin "16") (pinfunction "PA05_16") (pintype "bidirectional"))
    )
    (net (code "189") (name "~{EDISON_SPI_CS_1V8}") (class "Default")
      (node (ref "J13") (pin "2") (pinfunction "2_2") (pintype "passive"))
      (node (ref "J7") (pin "13") (pinfunction "13_13") (pintype "passive"))
      (node (ref "U10") (pin "5") (pinfunction "A4_5") (pintype "bidirectional"))
    )
    (net (code "190") (name "~{EDISON_SPI_CS}") (class "Default")
      (node (ref "U10") (pin "16") (pinfunction "B4_16") (pintype "bidirectional"))
      (node (ref "U6") (pin "56") (pinfunction "PA22_56") (pintype "bidirectional"))
    )
    (net (code "191") (name "~{ENABLE_LINUX}") (class "Default")
      (node (ref "Q1") (pin "G1") (pinfunction "G1_G1") (pintype "input"))
      (node (ref "U6") (pin "21") (pinfunction "PA06_21") (pintype "bidirectional"))
    )
    (net (code "192") (name "~{FRAM_CS}") (class "Default")
      (node (ref "J7") (pin "9") (pinfunction "9_9") (pintype "passive"))
      (node (ref "U1") (pin "1") (pinfunction "~{CS}_1") (pintype "bidirectional"))
      (node (ref "U7") (pin "62") (pinfunction "PA25_62") (pintype "bidirectional"))
    )
    (net (code "193") (name "~{SD_CS}") (class "Default")
      (node (ref "J1") (pin "2") (pinfunction "DATA3-CD/CS_N_2") (pintype "bidirectional"))
      (node (ref "J7") (pin "4") (pinfunction "4_4") (pintype "passive"))
      (node (ref "R13") (pin "1") (pinfunction "1_1") (pintype "passive"))
      (node (ref "U6") (pin "40") (pinfunction "PA13_40") (pintype "bidirectional"))
    )
    (net (code "194") (name "~{SD_DETECT}") (class "Default")
      (node (ref "J1") (pin "A") (pinfunction "A_A") (pintype "bidirectional"))
      (node (ref "R20") (pin "1") (pinfunction "1_1") (pintype "passive"))
      (node (ref "U6") (pin "44") (pinfunction "PA17_44") (pintype "bidirectional"))
    )
    (net (code "195") (name "~{SMBALERT}") (class "Default")
      (node (ref "J4") (pin "6") (pinfunction "~{SMBALERT}_6") (pintype "bidirectional"))
      (node (ref "U7") (pin "63") (pinfunction "PA26_63") (pintype "bidirectional"))
    )
    (net (code "196") (name "~{STORAGE_CS}") (class "Default")
      (node (ref "J7") (pin "8") (pinfunction "8_8") (pintype "passive"))
      (node (ref "U6") (pin "29") (pinfunction "PA09_29") (pintype "bidirectional"))
      (node (ref "U7") (pin "54") (pinfunction "PB13_54") (pintype "bidirectional"))
    )
    (net (code "197") (name "~{STORAGE_LED}") (class "Default")
      (node (ref "R8") (pin "2") (pinfunction "2_2") (pintype "passive"))
      (node (ref "U6") (pin "22") (pinfunction "PA07_22") (pintype "bidirectional"))
    )
    (net (code "198") (name "~{STORAGE_RESET}") (class "Default")
      (node (ref "J14") (pin "3") (pinfunction "~{RESET}_3") (pintype "bidirectional"))
      (node (ref "J4") (pin "205") (pinfunction "DBG_~{RESET}_205") (pintype "bidirectional"))
      (node (ref "SW4") (pin "1") (pinfunction "P$1_1") (pintype "passive"))
      (node (ref "U4") (pin "1") (pinfunction "~{RST}_1") (pintype "bidirectional"))
      (node (ref "U6") (pin "4") (pinfunction "~{RESET}_4") (pintype "bidirectional"))
    )
    (net (code "199") (name "~{WATCHDOG}") (class "Default")
      (node (ref "J4") (pin "7") (pinfunction "~{WATCHDOG}_7") (pintype "bidirectional"))
      (node (ref "U7") (pin "27") (pinfunction "PB06_27") (pintype "bidirectional"))
    )
  )
)
